# MB_main.net
KiCad netlist of a schematic drawn in Altium Designer
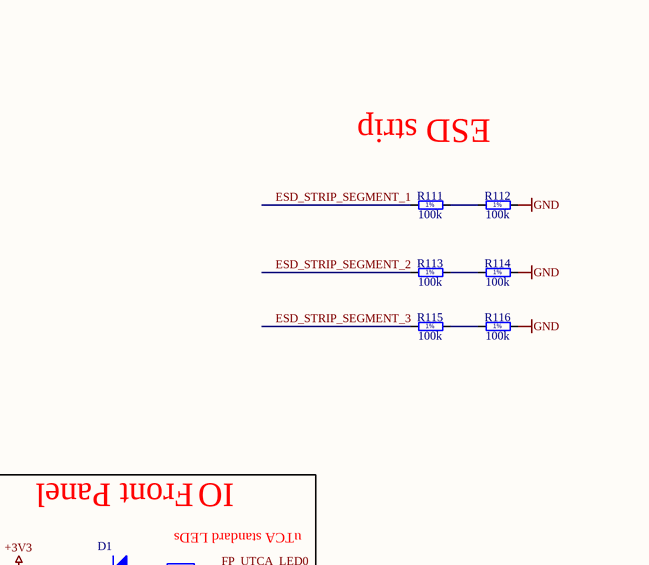
[diagram p0: MB_main.SchDoc, top left]
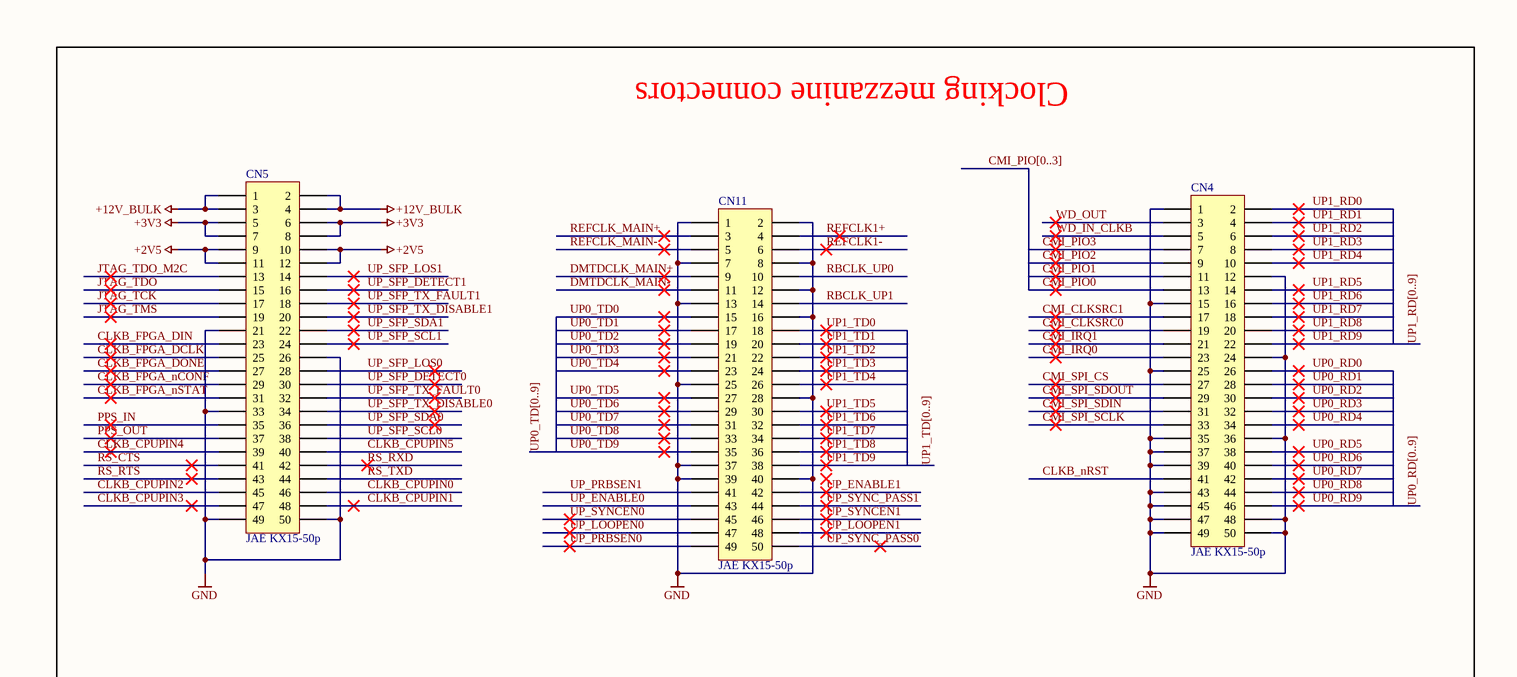
[diagram p1: MB_main.SchDoc, top middle]
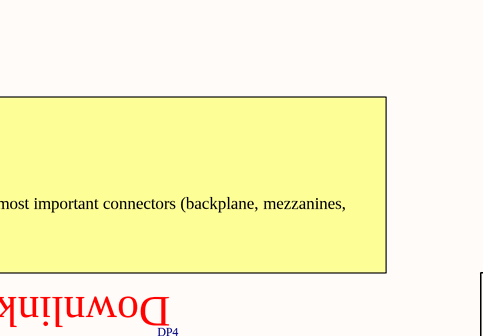
[diagram p2: MB_main.SchDoc, top right]
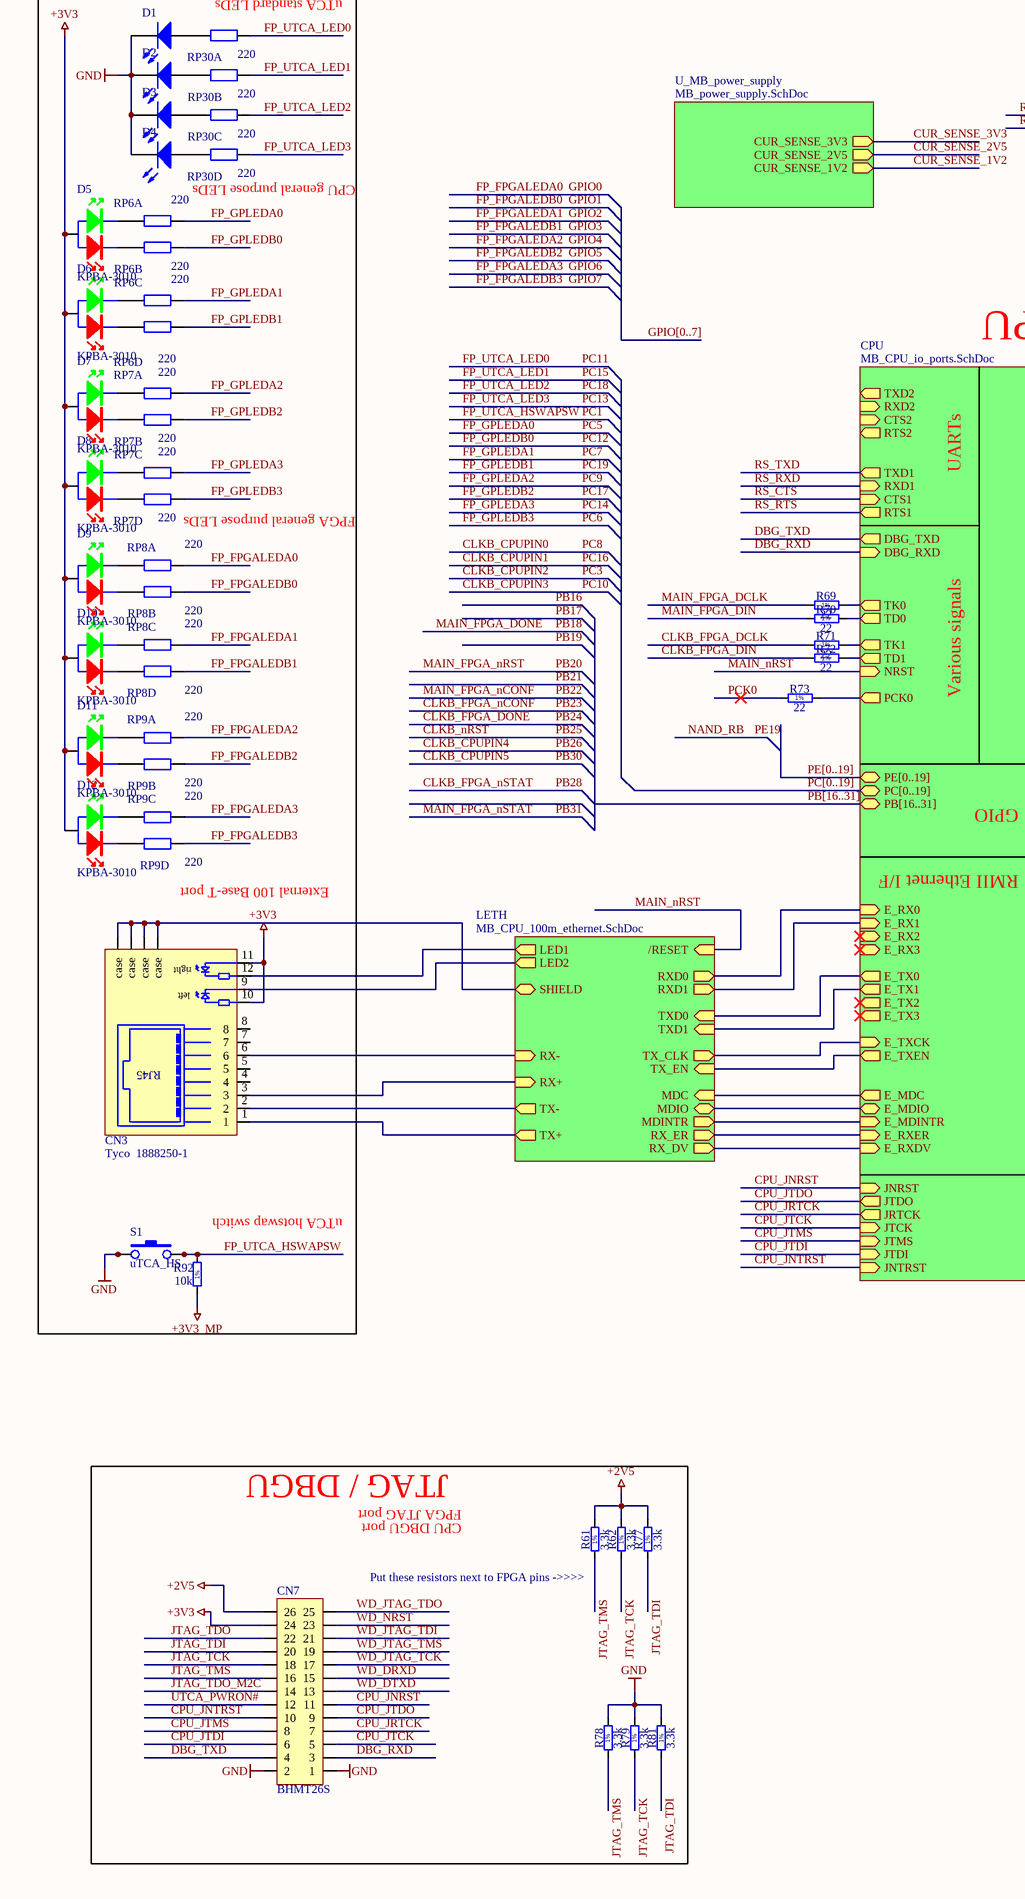
[diagram p3: MB_main.SchDoc, bottom left]
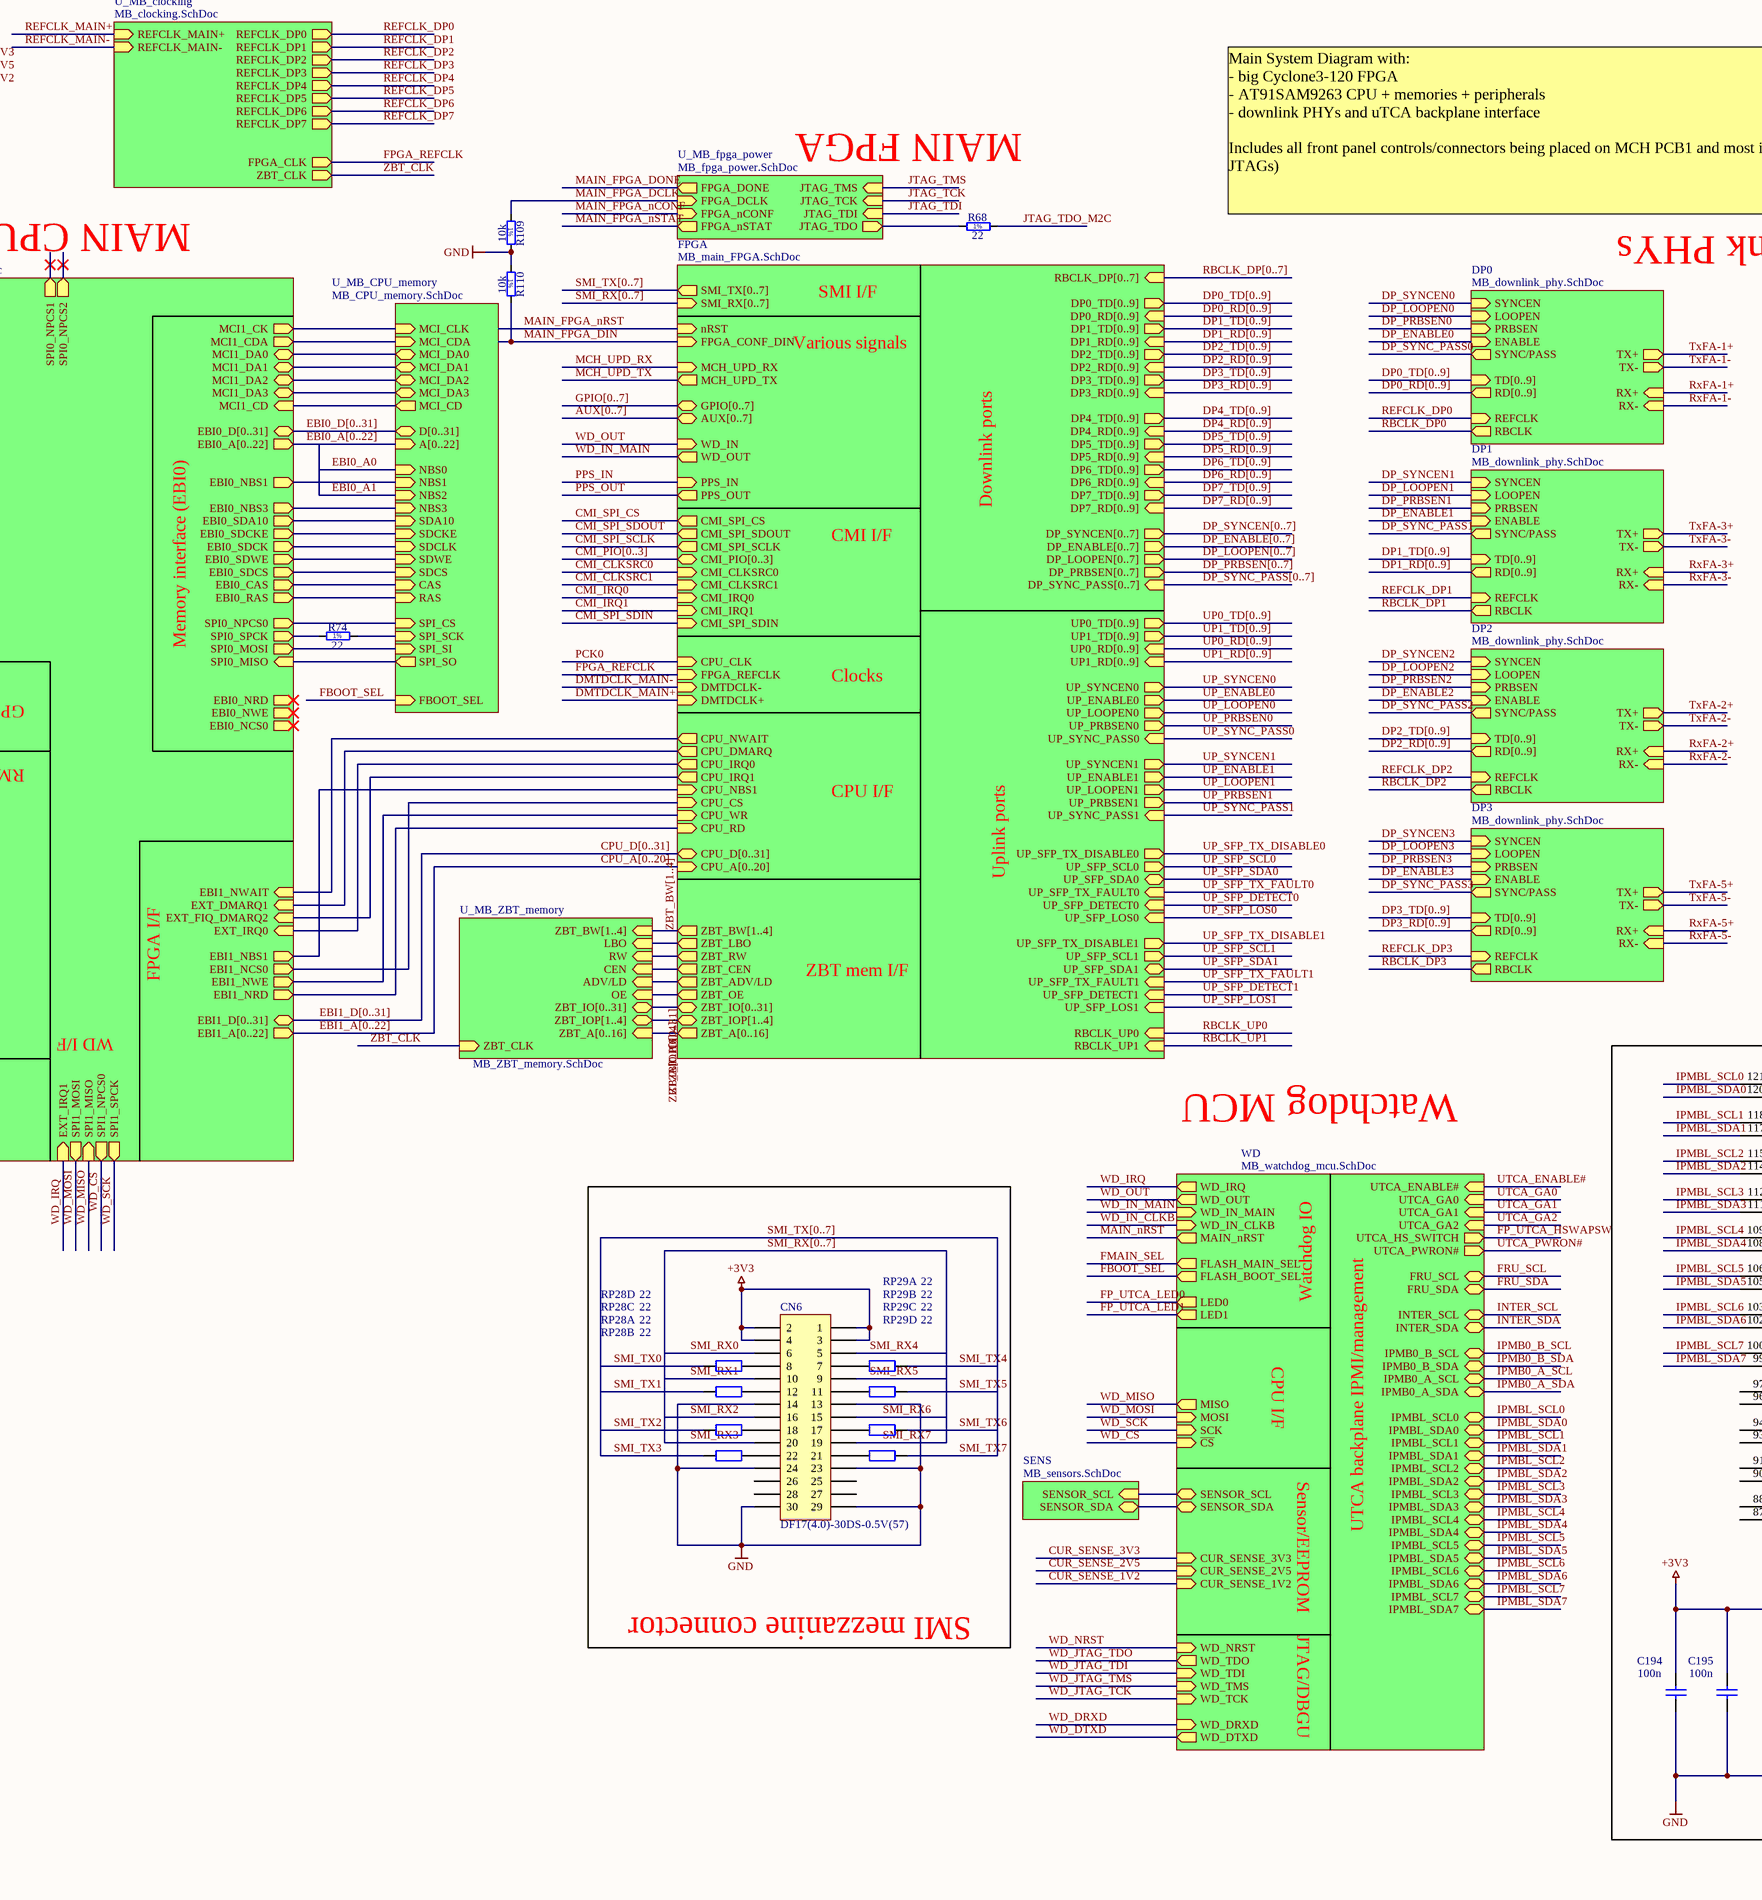
[diagram p4: MB_main.SchDoc, bottom middle]
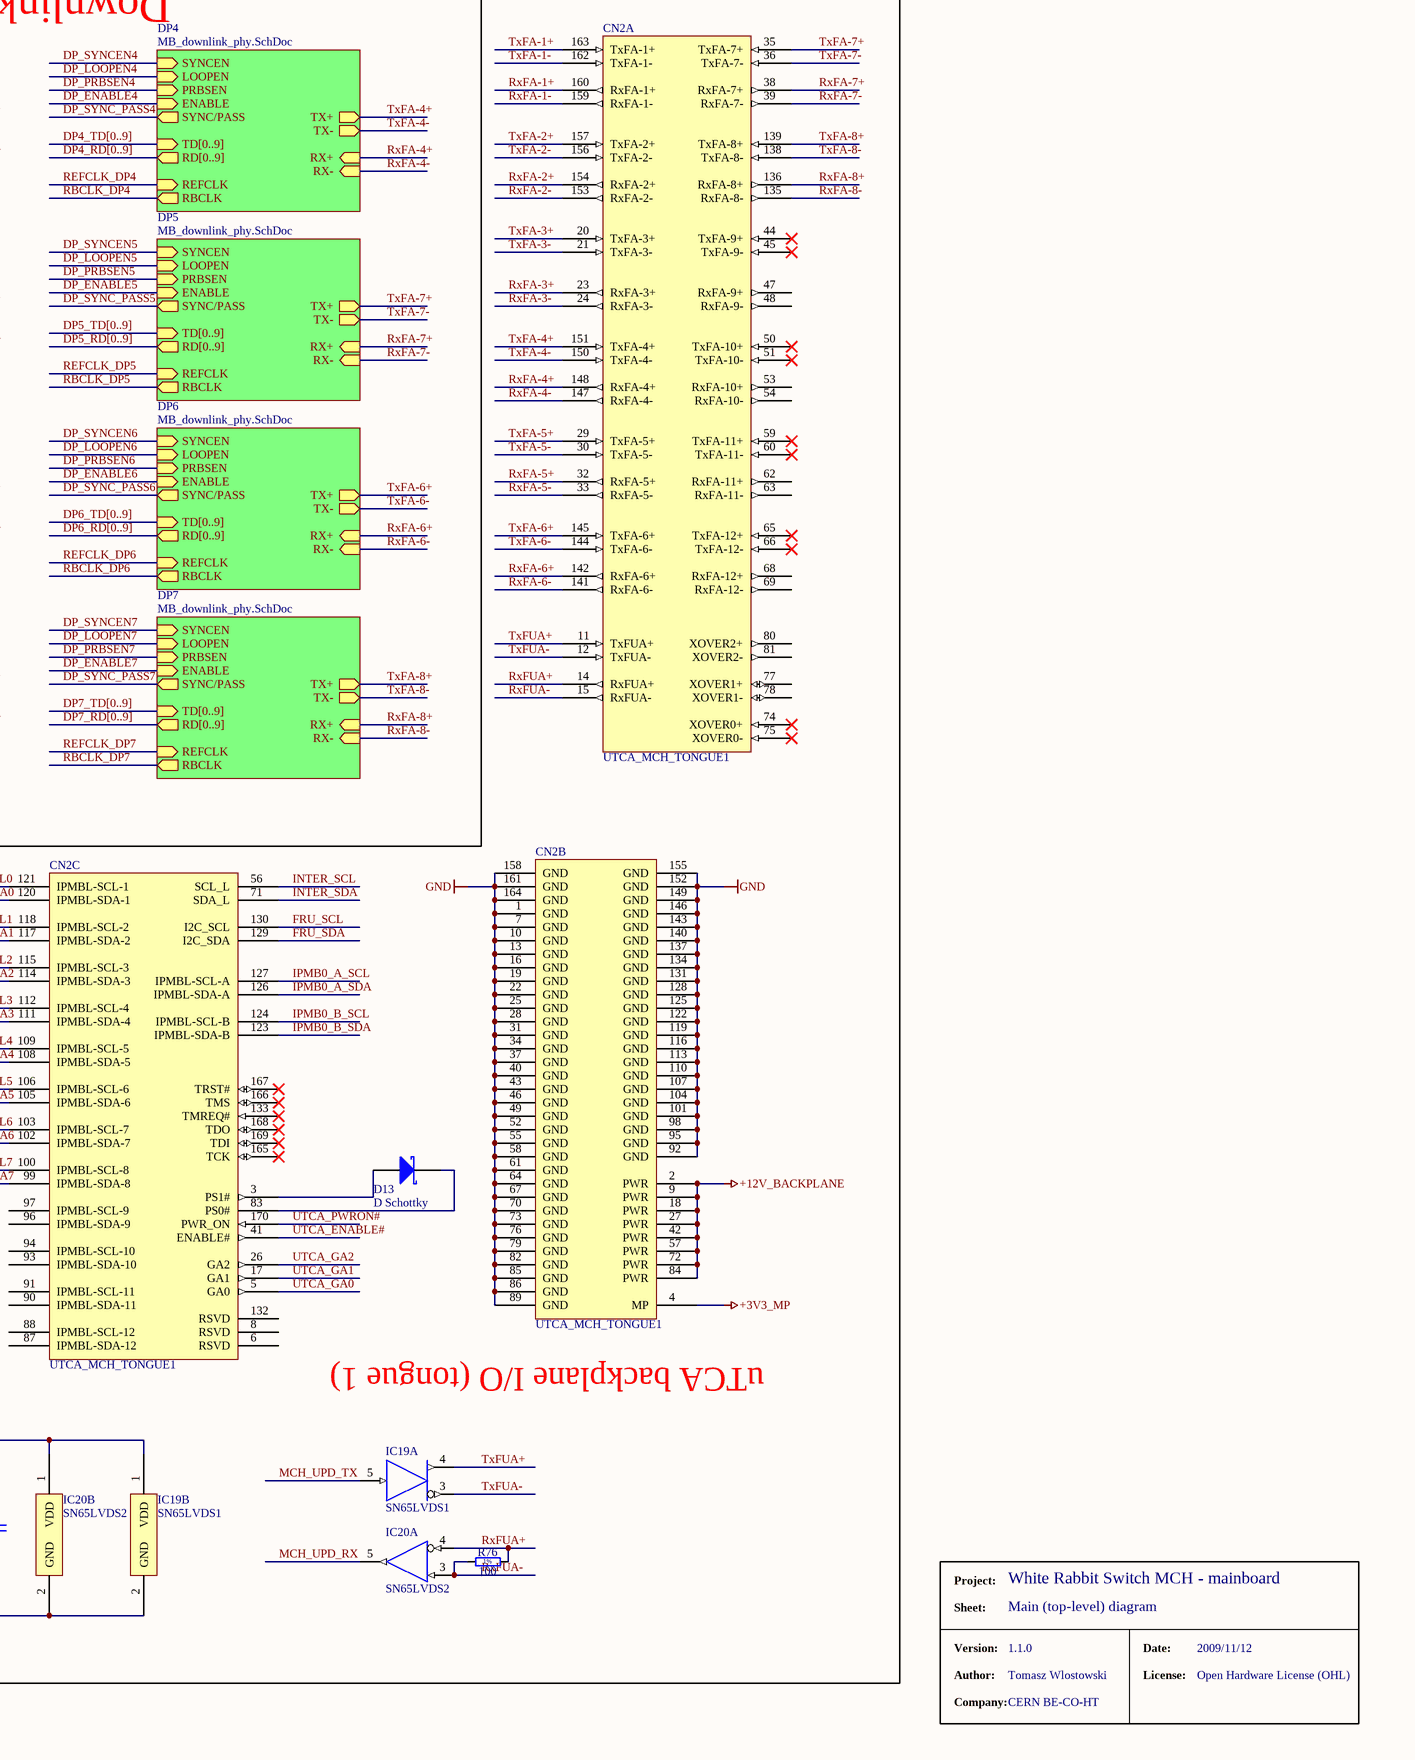
[diagram p5: MB_main.SchDoc, bottom right]

(export (version "E")
  (design (tool "Eeschema 10.0.6"))
  (components
    (comp (ref "C194")
      (value "100n")
      (footprint "CAPC1005X55N")
      (description "Non-polarised capacitor")
      (fields
        (field (name "PART NUMBER") "CC0402_100NF_16V_10%_X7R")
        (field (name "VOLTAGE") "16V")
        (field (name "AUTHOR") "CERN DEM JLC")
      )
      (libsource (lib "Capacitors") (part "Capacitor - non polarized"))
    )
    (comp (ref "C195")
      (value "100n")
      (footprint "CAPC1005X55N")
      (description "Non-polarised capacitor")
      (fields
        (field (name "PART NUMBER") "CC0402_100NF_16V_10%_X7R")
        (field (name "VOLTAGE") "16V")
        (field (name "AUTHOR") "CERN DEM JLC")
      )
      (libsource (lib "Capacitors") (part "Capacitor - non polarized"))
    )
    (comp (ref "CN2")
      (value "UTCA_MCH_TONGUE1")
      (description "microTCA MTCA.0 standard MCH connector 1")
      (libsource (lib "wr_switch") (part "UTCA_MCH_TONGUE1"))
    )
    (comp (ref "CN3")
      (value "Tyco  1888250-1")
      (footprint "TYCO_ETHERNET_1888250-1")
      (description "low profile uTCA Ethernet jack (RJ45)")
      (libsource (lib "wr_switch") (part "CON_ETHERNET_TYCO_1888250-1"))
    )
    (comp (ref "CN4")
      (value "JAE KX15-50p")
      (footprint "JAE_KX15_50P")
      (description "multipin B2B connector (plug)")
      (libsource (lib "wr_switch") (part "KX15_50p"))
    )
    (comp (ref "CN5")
      (value "JAE KX15-50p")
      (footprint "JAE_KX15_50P")
      (description "multipin B2B connector (plug)")
      (libsource (lib "wr_switch") (part "KX15_50p"))
    )
    (comp (ref "CN6")
      (value "DF17(4.0)-30DS-0.5V(57)")
      (footprint "DF17-30-SOCKET")
      (description "multipin B2B connector (plug)")
      (libsource (lib "wr_switch") (part "KX15_30p"))
    )
    (comp (ref "CN7")
      (value "BHMT26S")
      (footprint "CONN_HDR_SMD_2mm_2x13")
      (description "1.27 mm dual row goldpin")
      (libsource (lib "wr_switch") (part "CONN_2x13 2"))
    )
    (comp (ref "CN11")
      (value "JAE KX15-50p")
      (footprint "JAE_KX15_50P")
      (description "multipin B2B connector (plug)")
      (libsource (lib "wr_switch") (part "KX15_50p"))
    )
    (comp (ref "D1")
      (value "LED red")
      (footprint "CD1608-0603")
      (description "Chip LED (any color)")
      (fields (field (name "PUBLISHER") "Altium Limited"))
      (libsource (lib "wr_switch") (part "LED0"))
    )
    (comp (ref "D2")
      (value "LED green")
      (footprint "CD1608-0603")
      (description "Chip LED (any color)")
      (fields (field (name "PUBLISHER") "Altium Limited"))
      (libsource (lib "wr_switch") (part "LED0"))
    )
    (comp (ref "D3")
      (value "LED blue")
      (footprint "CD1608-0603")
      (description "Chip LED (any color)")
      (fields (field (name "PUBLISHER") "Altium Limited"))
      (libsource (lib "wr_switch") (part "LED0"))
    )
    (comp (ref "D4")
      (value "LED orange")
      (footprint "CD1608-0603")
      (description "Chip LED (any color)")
      (fields (field (name "PUBLISHER") "Altium Limited"))
      (libsource (lib "wr_switch") (part "LED0"))
    )
    (comp (ref "D5")
      (value "KPBA-3010")
      (footprint "footprints:DUOLED_LNJ123")
      (description "Dual color LED")
      (libsource (lib "wr_switch") (part "LED_2_colour"))
    )
    (comp (ref "D6")
      (value "KPBA-3010")
      (footprint "footprints:DUOLED_LNJ123")
      (description "Dual color LED")
      (libsource (lib "wr_switch") (part "LED_2_colour"))
    )
    (comp (ref "D7")
      (value "KPBA-3010")
      (footprint "footprints:DUOLED_LNJ123")
      (description "Dual color LED")
      (libsource (lib "wr_switch") (part "LED_2_colour"))
    )
    (comp (ref "D8")
      (value "KPBA-3010")
      (footprint "footprints:DUOLED_LNJ123")
      (description "Dual color LED")
      (libsource (lib "wr_switch") (part "LED_2_colour"))
    )
    (comp (ref "D9")
      (value "KPBA-3010")
      (footprint "footprints:DUOLED_LNJ123")
      (description "Dual color LED")
      (libsource (lib "wr_switch") (part "LED_2_colour"))
    )
    (comp (ref "D10")
      (value "KPBA-3010")
      (footprint "footprints:DUOLED_LNJ123")
      (description "Dual color LED")
      (libsource (lib "wr_switch") (part "LED_2_colour"))
    )
    (comp (ref "D11")
      (value "KPBA-3010")
      (footprint "footprints:DUOLED_LNJ123")
      (description "Dual color LED")
      (libsource (lib "wr_switch") (part "LED_2_colour"))
    )
    (comp (ref "D12")
      (value "KPBA-3010")
      (footprint "footprints:DUOLED_LNJ123")
      (description "Dual color LED")
      (libsource (lib "wr_switch") (part "LED_2_colour"))
    )
    (comp (ref "D13")
      (value "D Schottky")
      (footprint "CD2012-0805")
      (description "Schottky Diode")
      (fields (field (name "PUBLISHER") "Altium Limited"))
      (libsource (lib "wr_switch") (part "D Schottky"))
    )
    (comp (ref "IC19")
      (value "SN65LVDS1")
      (footprint "SOT23-5AL")
      (description "TTL->LVDS buffer")
      (libsource (lib "wr_switch") (part "SN65LVDS1"))
    )
    (comp (ref "IC20")
      (value "SN65LVDS2")
      (footprint "SOT23-5AL")
      (description "LVDS->TTL buffer")
      (libsource (lib "wr_switch") (part "SN65LVDS2"))
    )
    (comp (ref "R61")
      (value "3.3k")
      (footprint "RESC1005X40N")
      (description "Resistor - 1%")
      (fields
        (field (name "PART NUMBER") "R0402_3K3_1%_0.0625W_100PPM")
        (field (name "POWER") "0.0625W")
        (field (name "AUTHOR") "CERN DEM JLC")
      )
      (libsource (lib "Resistors") (part "Resistor - 1%"))
    )
    (comp (ref "R62")
      (value "3.3k")
      (footprint "RESC1005X40N")
      (description "Resistor - 1%")
      (fields
        (field (name "PART NUMBER") "R0402_3K3_1%_0.0625W_100PPM")
        (field (name "POWER") "0.0625W")
        (field (name "AUTHOR") "CERN DEM JLC")
      )
      (libsource (lib "Resistors") (part "Resistor - 1%"))
    )
    (comp (ref "R68")
      (value "22")
      (footprint "RESC1005X40N")
      (description "Resistor - 1%")
      (fields
        (field (name "PART NUMBER") "R0402_22R_1%_0.0625W_100PPM")
        (field (name "POWER") "0.0625W")
        (field (name "AUTHOR") "CERN DEM JLC")
      )
      (libsource (lib "Resistors") (part "Resistor - 1%"))
    )
    (comp (ref "R69")
      (value "22")
      (footprint "RESC1005X40N")
      (description "Resistor - 1%")
      (fields
        (field (name "PART NUMBER") "R0402_22R_1%_0.0625W_100PPM")
        (field (name "POWER") "0.0625W")
        (field (name "AUTHOR") "CERN DEM JLC")
      )
      (libsource (lib "Resistors") (part "Resistor - 1%"))
    )
    (comp (ref "R70")
      (value "22")
      (footprint "RESC1005X40N")
      (description "Resistor - 1%")
      (fields
        (field (name "PART NUMBER") "R0402_22R_1%_0.0625W_100PPM")
        (field (name "POWER") "0.0625W")
        (field (name "AUTHOR") "CERN DEM JLC")
      )
      (libsource (lib "Resistors") (part "Resistor - 1%"))
    )
    (comp (ref "R71")
      (value "22")
      (footprint "RESC1005X40N")
      (description "Resistor - 1%")
      (fields
        (field (name "PART NUMBER") "R0402_22R_1%_0.0625W_100PPM")
        (field (name "POWER") "0.0625W")
        (field (name "AUTHOR") "CERN DEM JLC")
      )
      (libsource (lib "Resistors") (part "Resistor - 1%"))
    )
    (comp (ref "R72")
      (value "22")
      (footprint "RESC1005X40N")
      (description "Resistor - 1%")
      (fields
        (field (name "PART NUMBER") "R0402_22R_1%_0.0625W_100PPM")
        (field (name "POWER") "0.0625W")
        (field (name "AUTHOR") "CERN DEM JLC")
      )
      (libsource (lib "Resistors") (part "Resistor - 1%"))
    )
    (comp (ref "R73")
      (value "22")
      (footprint "RESC1005X40N")
      (description "Resistor - 1%")
      (fields
        (field (name "PART NUMBER") "R0402_22R_1%_0.0625W_100PPM")
        (field (name "POWER") "0.0625W")
        (field (name "AUTHOR") "CERN DEM JLC")
      )
      (libsource (lib "Resistors") (part "Resistor - 1%"))
    )
    (comp (ref "R74")
      (value "22")
      (footprint "RESC1005X40N")
      (description "Resistor - 1%")
      (fields
        (field (name "PART NUMBER") "R0402_22R_1%_0.0625W_100PPM")
        (field (name "POWER") "0.0625W")
        (field (name "AUTHOR") "CERN DEM JLC")
      )
      (libsource (lib "Resistors") (part "Resistor - 1%"))
    )
    (comp (ref "R76")
      (value "100")
      (footprint "RESC1005X40N")
      (description "Resistor - 1%")
      (fields
        (field (name "PART NUMBER") "R0402_100R_1%_0.0625W_100PPM")
        (field (name "POWER") "0.0625W")
        (field (name "AUTHOR") "CERN DEM JLC")
      )
      (libsource (lib "Resistors") (part "Resistor - 1%"))
    )
    (comp (ref "R77")
      (value "3.3k")
      (footprint "RESC1005X40N")
      (description "Resistor - 1%")
      (fields
        (field (name "PART NUMBER") "R0402_3K3_1%_0.0625W_100PPM")
        (field (name "POWER") "0.0625W")
        (field (name "AUTHOR") "CERN DEM JLC")
      )
      (libsource (lib "Resistors") (part "Resistor - 1%"))
    )
    (comp (ref "R78")
      (value "3.3k")
      (footprint "RESC1005X40N")
      (description "Resistor - 1%")
      (fields
        (field (name "PART NUMBER") "R0402_3K3_1%_0.0625W_100PPM")
        (field (name "POWER") "0.0625W")
        (field (name "AUTHOR") "CERN DEM JLC")
      )
      (libsource (lib "Resistors") (part "Resistor - 1%"))
    )
    (comp (ref "R79")
      (value "3.3k")
      (footprint "RESC1005X40N")
      (description "Resistor - 1%")
      (fields
        (field (name "PART NUMBER") "R0402_3K3_1%_0.0625W_100PPM")
        (field (name "POWER") "0.0625W")
        (field (name "AUTHOR") "CERN DEM JLC")
      )
      (libsource (lib "Resistors") (part "Resistor - 1%"))
    )
    (comp (ref "R81")
      (value "3.3k")
      (footprint "RESC1005X40N")
      (description "Resistor - 1%")
      (fields
        (field (name "PART NUMBER") "R0402_3K3_1%_0.0625W_100PPM")
        (field (name "POWER") "0.0625W")
        (field (name "AUTHOR") "CERN DEM JLC")
      )
      (libsource (lib "Resistors") (part "Resistor - 1%"))
    )
    (comp (ref "R92")
      (value "10k")
      (footprint "RESC1005X40N")
      (description "Resistor - 1%")
      (fields
        (field (name "PART NUMBER") "R0402_10K_1%_0.0625W_100PPM")
        (field (name "POWER") "0.0625W")
        (field (name "AUTHOR") "CERN DEM JLC")
      )
      (libsource (lib "Resistors") (part "Resistor - 1%"))
    )
    (comp (ref "R109")
      (value "10k")
      (footprint "RESC1005X40N")
      (description "Resistor - 1%")
      (fields
        (field (name "PART NUMBER") "R0402_10K_1%_0.0625W_100PPM")
        (field (name "POWER") "0.0625W")
        (field (name "AUTHOR") "CERN DEM JLC")
      )
      (libsource (lib "Resistors") (part "Resistor - 1%"))
    )
    (comp (ref "R110")
      (value "10k")
      (footprint "RESC1005X40N")
      (description "Resistor - 1%")
      (fields
        (field (name "PART NUMBER") "R0402_10K_1%_0.0625W_100PPM")
        (field (name "POWER") "0.0625W")
        (field (name "AUTHOR") "CERN DEM JLC")
      )
      (libsource (lib "Resistors") (part "Resistor - 1%"))
    )
    (comp (ref "R111")
      (value "100k")
      (footprint "RESC3216X65N")
      (description "Resistor - 1%")
      (fields
        (field (name "PART NUMBER") "R1206_100K_1%_0.25W_100PPM")
        (field (name "POWER") "0.25W")
        (field (name "AUTHOR") "CERN DEM JLC")
      )
      (libsource (lib "Resistors") (part "Resistor - 1%"))
    )
    (comp (ref "R112")
      (value "100k")
      (footprint "RESC3216X65N")
      (description "Resistor - 1%")
      (fields
        (field (name "PART NUMBER") "R1206_100K_1%_0.25W_100PPM")
        (field (name "POWER") "0.25W")
        (field (name "AUTHOR") "CERN DEM JLC")
      )
      (libsource (lib "Resistors") (part "Resistor - 1%"))
    )
    (comp (ref "R113")
      (value "100k")
      (footprint "RESC3216X65N")
      (description "Resistor - 1%")
      (fields
        (field (name "PART NUMBER") "R1206_100K_1%_0.25W_100PPM")
        (field (name "POWER") "0.25W")
        (field (name "AUTHOR") "CERN DEM JLC")
      )
      (libsource (lib "Resistors") (part "Resistor - 1%"))
    )
    (comp (ref "R114")
      (value "100k")
      (footprint "RESC3216X65N")
      (description "Resistor - 1%")
      (fields
        (field (name "PART NUMBER") "R1206_100K_1%_0.25W_100PPM")
        (field (name "POWER") "0.25W")
        (field (name "AUTHOR") "CERN DEM JLC")
      )
      (libsource (lib "Resistors") (part "Resistor - 1%"))
    )
    (comp (ref "R115")
      (value "100k")
      (footprint "RESC3216X65N")
      (description "Resistor - 1%")
      (fields
        (field (name "PART NUMBER") "R1206_100K_1%_0.25W_100PPM")
        (field (name "POWER") "0.25W")
        (field (name "AUTHOR") "CERN DEM JLC")
      )
      (libsource (lib "Resistors") (part "Resistor - 1%"))
    )
    (comp (ref "R116")
      (value "100k")
      (footprint "RESC3216X65N")
      (description "Resistor - 1%")
      (fields
        (field (name "PART NUMBER") "R1206_100K_1%_0.25W_100PPM")
        (field (name "POWER") "0.25W")
        (field (name "AUTHOR") "CERN DEM JLC")
      )
      (libsource (lib "Resistors") (part "Resistor - 1%"))
    )
    (comp (ref "RP6")
      (value "220")
      (footprint "YC124")
      (description "4-resistor pack")
      (fields (field (name "Comment") "220R 0804"))
      (libsource (lib "wr_switch") (part "Res_Pack4_220R_YC124_1"))
    )
    (comp (ref "RP7")
      (value "220")
      (footprint "YC124")
      (description "4-resistor pack")
      (fields (field (name "Comment") "220R 0804"))
      (libsource (lib "wr_switch") (part "Res_Pack4_220R_YC124_1"))
    )
    (comp (ref "RP8")
      (value "220")
      (footprint "YC124")
      (description "4-resistor pack")
      (fields (field (name "Comment") "220R 0804"))
      (libsource (lib "wr_switch") (part "Res_Pack4_220R_YC124_1"))
    )
    (comp (ref "RP9")
      (value "220")
      (footprint "YC124")
      (description "4-resistor pack")
      (fields (field (name "Comment") "220R 0804"))
      (libsource (lib "wr_switch") (part "Res_Pack4_220R_YC124_1"))
    )
    (comp (ref "RP28")
      (value "22")
      (footprint "YC124")
      (description "4-resistor pack")
      (fields (field (name "Comment") "22R 0804"))
      (libsource (lib "wr_switch") (part "Res_Pack4_22R_YC124"))
    )
    (comp (ref "RP29")
      (value "22")
      (footprint "YC124")
      (description "4-resistor pack")
      (fields (field (name "Comment") "22R 0804"))
      (libsource (lib "wr_switch") (part "Res_Pack4_22R_YC124"))
    )
    (comp (ref "RP30")
      (value "220")
      (footprint "YC124")
      (description "4-resistor pack")
      (fields (field (name "Comment") "220R 0804"))
      (libsource (lib "wr_switch") (part "Res_Pack4_220R_YC124_1"))
    )
    (comp (ref "S1")
      (value "uTCA_HS")
      (footprint "uTCA_HOTSWAP_SWITCH")
      (description "Push button")
      (libsource (lib "wr_switch") (part "uTCA_HOTSWAP_SWITCH"))
    )
  )
  (nets
    (net (code "356") (name "+2V5") (class "Default")
      (node (ref "CN5") (pin "10") (pinfunction "10_10") (pintype "passive"))
      (node (ref "CN5") (pin "11") (pinfunction "11_11") (pintype "passive"))
      (node (ref "CN5") (pin "12") (pinfunction "12_12") (pintype "passive"))
      (node (ref "CN5") (pin "9") (pinfunction "9_9") (pintype "passive"))
      (node (ref "CN7") (pin "26") (pinfunction "26_26") (pintype "passive"))
      (node (ref "R61") (pin "2") (pinfunction "2_2") (pintype "passive"))
      (node (ref "R62") (pin "2") (pinfunction "2_2") (pintype "passive"))
      (node (ref "R77") (pin "2") (pinfunction "2_2") (pintype "passive"))
    )
    (net (code "357") (name "+3V3") (class "Default")
      (node (ref "C194") (pin "2") (pinfunction "2_2") (pintype "passive"))
      (node (ref "C195") (pin "2") (pinfunction "2_2") (pintype "passive"))
      (node (ref "CN3") (pin "10") (pinfunction "D1_10") (pintype "passive"))
      (node (ref "CN3") (pin "11") (pinfunction "D4_11") (pintype "passive"))
      (node (ref "CN5") (pin "5") (pinfunction "5_5") (pintype "passive"))
      (node (ref "CN5") (pin "6") (pinfunction "6_6") (pintype "passive"))
      (node (ref "CN5") (pin "7") (pinfunction "7_7") (pintype "passive"))
      (node (ref "CN5") (pin "8") (pinfunction "8_8") (pintype "passive"))
      (node (ref "CN6") (pin "1") (pinfunction "1_1") (pintype "passive"))
      (node (ref "CN6") (pin "2") (pinfunction "2_2") (pintype "passive"))
      (node (ref "CN6") (pin "3") (pinfunction "3_3") (pintype "passive"))
      (node (ref "CN6") (pin "4") (pinfunction "4_4") (pintype "passive"))
      (node (ref "CN7") (pin "24") (pinfunction "24_24") (pintype "passive"))
      (node (ref "D10") (pin "A") (pinfunction "A_A") (pintype "passive"))
      (node (ref "D11") (pin "A") (pinfunction "A_A") (pintype "passive"))
      (node (ref "D12") (pin "A") (pinfunction "A_A") (pintype "passive"))
      (node (ref "D5") (pin "A") (pinfunction "A_A") (pintype "passive"))
      (node (ref "D6") (pin "A") (pinfunction "A_A") (pintype "passive"))
      (node (ref "D7") (pin "A") (pinfunction "A_A") (pintype "passive"))
      (node (ref "D8") (pin "A") (pinfunction "A_A") (pintype "passive"))
      (node (ref "D9") (pin "A") (pinfunction "A_A") (pintype "passive"))
      (node (ref "IC19") (pin "1") (pinfunction "VDD_1") (pintype "passive"))
      (node (ref "IC20") (pin "1") (pinfunction "VDD_1") (pintype "passive"))
    )
    (net (code "358") (name "+3V3_MP") (class "Default")
      (node (ref "CN2") (pin "4") (pinfunction "MP_4") (pintype "power_in"))
      (node (ref "R92") (pin "1") (pinfunction "1_1") (pintype "passive"))
    )
    (net (code "359") (name "+12V_BACKPLANE") (class "Default")
      (node (ref "CN2") (pin "18") (pinfunction "PWR_18") (pintype "power_in"))
      (node (ref "CN2") (pin "2") (pinfunction "PWR_2") (pintype "power_in"))
      (node (ref "CN2") (pin "27") (pinfunction "PWR_27") (pintype "power_in"))
      (node (ref "CN2") (pin "42") (pinfunction "PWR_42") (pintype "power_in"))
      (node (ref "CN2") (pin "57") (pinfunction "PWR_57") (pintype "power_in"))
      (node (ref "CN2") (pin "72") (pinfunction "PWR_72") (pintype "power_in"))
      (node (ref "CN2") (pin "84") (pinfunction "PWR_84") (pintype "power_in"))
      (node (ref "CN2") (pin "9") (pinfunction "PWR_9") (pintype "power_in"))
    )
    (net (code "360") (name "+12V_BULK") (class "Default")
      (node (ref "CN5") (pin "1") (pinfunction "1_1") (pintype "passive"))
      (node (ref "CN5") (pin "2") (pinfunction "2_2") (pintype "passive"))
      (node (ref "CN5") (pin "3") (pinfunction "3_3") (pintype "passive"))
      (node (ref "CN5") (pin "4") (pinfunction "4_4") (pintype "passive"))
    )
    (net (code "362") (name "/CLKB_FPGA_DCLK") (class "Default")
      (node (ref "CN5") (pin "25") (pinfunction "25_25") (pintype "passive"))
      (node (ref "R71") (pin "1") (pinfunction "1_1") (pintype "passive"))
    )
    (net (code "363") (name "/CLKB_FPGA_DIN") (class "Default")
      (node (ref "CN5") (pin "23") (pinfunction "23_23") (pintype "passive"))
      (node (ref "R72") (pin "1") (pinfunction "1_1") (pintype "passive"))
    )
    (net (code "364") (name "/CMI_CLKSRC0") (class "Default")
      (node (ref "CN4") (pin "19") (pinfunction "19_19") (pintype "passive"))
    )
    (net (code "365") (name "/CMI_CLKSRC1") (class "Default")
      (node (ref "CN4") (pin "17") (pinfunction "17_17") (pintype "passive"))
    )
    (net (code "366") (name "/CMI_IRQ0") (class "Default")
      (node (ref "CN4") (pin "23") (pinfunction "23_23") (pintype "passive"))
    )
    (net (code "367") (name "/CMI_IRQ1") (class "Default")
      (node (ref "CN4") (pin "21") (pinfunction "21_21") (pintype "passive"))
    )
    (net (code "368") (name "/CMI_PIO0") (class "Default")
      (node (ref "CN4") (pin "13") (pinfunction "13_13") (pintype "passive"))
    )
    (net (code "369") (name "/CMI_PIO1") (class "Default")
      (node (ref "CN4") (pin "11") (pinfunction "11_11") (pintype "passive"))
    )
    (net (code "370") (name "/CMI_PIO2") (class "Default")
      (node (ref "CN4") (pin "9") (pinfunction "9_9") (pintype "passive"))
    )
    (net (code "371") (name "/CMI_PIO3") (class "Default")
      (node (ref "CN4") (pin "7") (pinfunction "7_7") (pintype "passive"))
    )
    (net (code "373") (name "/CMI_SPI_CS") (class "Default")
      (node (ref "CN4") (pin "27") (pinfunction "27_27") (pintype "passive"))
    )
    (net (code "374") (name "/CMI_SPI_SCLK") (class "Default")
      (node (ref "CN4") (pin "33") (pinfunction "33_33") (pintype "passive"))
    )
    (net (code "375") (name "/CMI_SPI_SDIN") (class "Default")
      (node (ref "CN4") (pin "31") (pinfunction "31_31") (pintype "passive"))
    )
    (net (code "376") (name "/CMI_SPI_SDOUT") (class "Default")
      (node (ref "CN4") (pin "29") (pinfunction "29_29") (pintype "passive"))
    )
    (net (code "382") (name "/CPU_JNRST") (class "Default")
      (node (ref "CN7") (pin "11") (pinfunction "11_11") (pintype "passive"))
    )
    (net (code "383") (name "/CPU_JNTRST") (class "Default")
      (node (ref "CN7") (pin "10") (pinfunction "10_10") (pintype "passive"))
    )
    (net (code "384") (name "/CPU_JRTCK") (class "Default")
      (node (ref "CN7") (pin "7") (pinfunction "7_7") (pintype "passive"))
    )
    (net (code "385") (name "/CPU_JTCK") (class "Default")
      (node (ref "CN7") (pin "5") (pinfunction "5_5") (pintype "passive"))
    )
    (net (code "386") (name "/CPU_JTDI") (class "Default")
      (node (ref "CN7") (pin "6") (pinfunction "6_6") (pintype "passive"))
    )
    (net (code "387") (name "/CPU_JTDO") (class "Default")
      (node (ref "CN7") (pin "9") (pinfunction "9_9") (pintype "passive"))
    )
    (net (code "388") (name "/CPU_JTMS") (class "Default")
      (node (ref "CN7") (pin "8") (pinfunction "8_8") (pintype "passive"))
    )
    (net (code "394") (name "/DBG_RXD") (class "Default")
      (node (ref "CN7") (pin "3") (pinfunction "3_3") (pintype "passive"))
    )
    (net (code "395") (name "/DBG_TXD") (class "Default")
      (node (ref "CN7") (pin "4") (pinfunction "4_4") (pintype "passive"))
    )
    (net (code "396") (name "/DMTDCLK_MAIN+") (class "Default")
      (node (ref "CN11") (pin "9") (pinfunction "9_9") (pintype "passive"))
    )
    (net (code "397") (name "/DMTDCLK_MAIN-") (class "Default")
      (node (ref "CN11") (pin "11") (pinfunction "11_11") (pintype "passive"))
    )
    (net (code "479") (name "/ESD_STRIP_SEGMENT_1") (class "Default")
      (node (ref "R111") (pin "1") (pinfunction "1_1") (pintype "passive"))
    )
    (net (code "480") (name "/ESD_STRIP_SEGMENT_2") (class "Default")
      (node (ref "R113") (pin "1") (pinfunction "1_1") (pintype "passive"))
    )
    (net (code "481") (name "/ESD_STRIP_SEGMENT_3") (class "Default")
      (node (ref "R115") (pin "1") (pinfunction "1_1") (pintype "passive"))
    )
    (net (code "494") (name "/FRU_SCL") (class "Default")
      (node (ref "CN2") (pin "130") (pinfunction "I2C_SCL_130") (pintype "open_collector"))
    )
    (net (code "495") (name "/FRU_SDA") (class "Default")
      (node (ref "CN2") (pin "129") (pinfunction "I2C_SDA_129") (pintype "open_collector"))
    )
    (net (code "496") (name "/GPIO0") (class "Default")
      (node (ref "RP8") (pin "8") (pinfunction "B_8") (pintype "passive"))
    )
    (net (code "497") (name "/GPIO1") (class "Default")
      (node (ref "RP8") (pin "7") (pinfunction "B_7") (pintype "passive"))
    )
    (net (code "498") (name "/GPIO2") (class "Default")
      (node (ref "RP8") (pin "6") (pinfunction "B_6") (pintype "passive"))
    )
    (net (code "499") (name "/GPIO3") (class "Default")
      (node (ref "RP8") (pin "5") (pinfunction "B_5") (pintype "passive"))
    )
    (net (code "500") (name "/GPIO4") (class "Default")
      (node (ref "RP9") (pin "8") (pinfunction "B_8") (pintype "passive"))
    )
    (net (code "501") (name "/GPIO5") (class "Default")
      (node (ref "RP9") (pin "7") (pinfunction "B_7") (pintype "passive"))
    )
    (net (code "502") (name "/GPIO6") (class "Default")
      (node (ref "RP9") (pin "6") (pinfunction "B_6") (pintype "passive"))
    )
    (net (code "503") (name "/GPIO7") (class "Default")
      (node (ref "RP9") (pin "5") (pinfunction "B_5") (pintype "passive"))
    )
    (net (code "505") (name "/INTER_SCL") (class "Default")
      (node (ref "CN2") (pin "56") (pinfunction "SCL_L_56") (pintype "open_collector"))
    )
    (net (code "506") (name "/INTER_SDA") (class "Default")
      (node (ref "CN2") (pin "71") (pinfunction "SDA_L_71") (pintype "open_collector"))
    )
    (net (code "507") (name "/IPMB0_A_SCL") (class "Default")
      (node (ref "CN2") (pin "127") (pinfunction "IPMBL-SCL-A_127") (pintype "open_collector"))
    )
    (net (code "508") (name "/IPMB0_A_SDA") (class "Default")
      (node (ref "CN2") (pin "126") (pinfunction "IPMBL-SDA-A_126") (pintype "open_collector"))
    )
    (net (code "509") (name "/IPMB0_B_SCL") (class "Default")
      (node (ref "CN2") (pin "124") (pinfunction "IPMBL-SCL-B_124") (pintype "open_collector"))
    )
    (net (code "510") (name "/IPMB0_B_SDA") (class "Default")
      (node (ref "CN2") (pin "123") (pinfunction "IPMBL-SDA-B_123") (pintype "open_collector"))
    )
    (net (code "511") (name "/IPMBL_SCL0") (class "Default")
      (node (ref "CN2") (pin "121") (pinfunction "IPMBL-SCL-1_121") (pintype "open_collector"))
    )
    (net (code "512") (name "/IPMBL_SCL1") (class "Default")
      (node (ref "CN2") (pin "118") (pinfunction "IPMBL-SCL-2_118") (pintype "open_collector"))
    )
    (net (code "513") (name "/IPMBL_SCL2") (class "Default")
      (node (ref "CN2") (pin "115") (pinfunction "IPMBL-SCL-3_115") (pintype "open_collector"))
    )
    (net (code "514") (name "/IPMBL_SCL3") (class "Default")
      (node (ref "CN2") (pin "112") (pinfunction "IPMBL-SCL-4_112") (pintype "open_collector"))
    )
    (net (code "515") (name "/IPMBL_SCL4") (class "Default")
      (node (ref "CN2") (pin "109") (pinfunction "IPMBL-SCL-5_109") (pintype "open_collector"))
    )
    (net (code "516") (name "/IPMBL_SCL5") (class "Default")
      (node (ref "CN2") (pin "106") (pinfunction "IPMBL-SCL-6_106") (pintype "open_collector"))
    )
    (net (code "517") (name "/IPMBL_SCL6") (class "Default")
      (node (ref "CN2") (pin "103") (pinfunction "IPMBL-SCL-7_103") (pintype "open_collector"))
    )
    (net (code "518") (name "/IPMBL_SCL7") (class "Default")
      (node (ref "CN2") (pin "100") (pinfunction "IPMBL-SCL-8_100") (pintype "open_collector"))
    )
    (net (code "519") (name "/IPMBL_SDA0") (class "Default")
      (node (ref "CN2") (pin "120") (pinfunction "IPMBL-SDA-1_120") (pintype "open_collector"))
    )
    (net (code "520") (name "/IPMBL_SDA1") (class "Default")
      (node (ref "CN2") (pin "117") (pinfunction "IPMBL-SDA-2_117") (pintype "open_collector"))
    )
    (net (code "521") (name "/IPMBL_SDA2") (class "Default")
      (node (ref "CN2") (pin "114") (pinfunction "IPMBL-SDA-3_114") (pintype "open_collector"))
    )
    (net (code "522") (name "/IPMBL_SDA3") (class "Default")
      (node (ref "CN2") (pin "111") (pinfunction "IPMBL-SDA-4_111") (pintype "open_collector"))
    )
    (net (code "523") (name "/IPMBL_SDA4") (class "Default")
      (node (ref "CN2") (pin "108") (pinfunction "IPMBL-SDA-5_108") (pintype "open_collector"))
    )
    (net (code "524") (name "/IPMBL_SDA5") (class "Default")
      (node (ref "CN2") (pin "105") (pinfunction "IPMBL-SDA-6_105") (pintype "open_collector"))
    )
    (net (code "525") (name "/IPMBL_SDA6") (class "Default")
      (node (ref "CN2") (pin "102") (pinfunction "IPMBL-SDA-7_102") (pintype "open_collector"))
    )
    (net (code "526") (name "/IPMBL_SDA7") (class "Default")
      (node (ref "CN2") (pin "99") (pinfunction "IPMBL-SDA-8_99") (pintype "open_collector"))
    )
    (net (code "527") (name "/JTAG_TCK") (class "Default")
      (node (ref "CN5") (pin "17") (pinfunction "17_17") (pintype "passive"))
      (node (ref "CN7") (pin "18") (pinfunction "18_18") (pintype "passive"))
      (node (ref "R62") (pin "1") (pinfunction "1_1") (pintype "passive"))
      (node (ref "R79") (pin "1") (pinfunction "1_1") (pintype "passive"))
    )
    (net (code "528") (name "/JTAG_TDI") (class "Default")
      (node (ref "CN7") (pin "20") (pinfunction "20_20") (pintype "passive"))
      (node (ref "R77") (pin "1") (pinfunction "1_1") (pintype "passive"))
      (node (ref "R81") (pin "1") (pinfunction "1_1") (pintype "passive"))
    )
    (net (code "529") (name "/JTAG_TDO") (class "Default")
      (node (ref "CN5") (pin "15") (pinfunction "15_15") (pintype "passive"))
      (node (ref "CN7") (pin "22") (pinfunction "22_22") (pintype "passive"))
    )
    (net (code "530") (name "/JTAG_TDO_1") (class "Default")
      (node (ref "R68") (pin "1") (pinfunction "1_1") (pintype "passive"))
    )
    (net (code "531") (name "/JTAG_TDO_M2C") (class "Default")
      (node (ref "CN5") (pin "13") (pinfunction "13_13") (pintype "passive"))
      (node (ref "CN7") (pin "14") (pinfunction "14_14") (pintype "passive"))
      (node (ref "R68") (pin "2") (pinfunction "2_2") (pintype "passive"))
    )
    (net (code "532") (name "/JTAG_TMS") (class "Default")
      (node (ref "CN5") (pin "19") (pinfunction "19_19") (pintype "passive"))
      (node (ref "CN7") (pin "16") (pinfunction "16_16") (pintype "passive"))
      (node (ref "R61") (pin "1") (pinfunction "1_1") (pintype "passive"))
      (node (ref "R78") (pin "1") (pinfunction "1_1") (pintype "passive"))
    )
    (net (code "533") (name "/LED1") (class "Default")
      (node (ref "CN3") (pin "12") (pinfunction "D3_12") (pintype "passive"))
    )
    (net (code "534") (name "/LED2") (class "Default")
      (node (ref "CN3") (pin "9") (pinfunction "D2_9") (pintype "passive"))
    )
    (net (code "535") (name "/MAIN_FPGA_DCLK") (class "Default")
      (node (ref "R109") (pin "1") (pinfunction "1_1") (pintype "passive"))
      (node (ref "R69") (pin "1") (pinfunction "1_1") (pintype "passive"))
    )
    (net (code "536") (name "/MAIN_FPGA_DIN") (class "Default")
      (node (ref "R110") (pin "2") (pinfunction "2_2") (pintype "passive"))
      (node (ref "R70") (pin "1") (pinfunction "1_1") (pintype "passive"))
    )
    (net (code "538") (name "/MCH_UPD_RX") (class "Default")
      (node (ref "IC20") (pin "5") (pinfunction "Q_5") (pintype "output"))
    )
    (net (code "539") (name "/MCH_UPD_TX") (class "Default")
      (node (ref "IC19") (pin "5") (pinfunction "A_5") (pintype "input"))
    )
    (net (code "555") (name "/PB23") (class "Default")
      (node (ref "CN5") (pin "29") (pinfunction "29_29") (pintype "passive"))
    )
    (net (code "556") (name "/PB24") (class "Default")
      (node (ref "CN5") (pin "27") (pinfunction "27_27") (pintype "passive"))
    )
    (net (code "557") (name "/PB25") (class "Default")
      (node (ref "CN4") (pin "41") (pinfunction "41_41") (pintype "passive"))
    )
    (net (code "558") (name "/PB26") (class "Default")
      (node (ref "CN5") (pin "39") (pinfunction "39_39") (pintype "passive"))
    )
    (net (code "559") (name "/PB28") (class "Default")
      (node (ref "CN5") (pin "31") (pinfunction "31_31") (pintype "passive"))
    )
    (net (code "560") (name "/PB30") (class "Default")
      (node (ref "CN5") (pin "40") (pinfunction "40_40") (pintype "passive"))
    )
    (net (code "563") (name "/PC1") (class "Default")
      (node (ref "R92") (pin "2") (pinfunction "2_2") (pintype "passive"))
      (node (ref "S1") (pin "B") (pinfunction "B_B") (pintype "passive"))
      (node (ref "S1") (pin "D") (pinfunction "D_D") (pintype "passive"))
    )
    (net (code "564") (name "/PC3") (class "Default")
      (node (ref "CN5") (pin "45") (pinfunction "45_45") (pintype "passive"))
    )
    (net (code "565") (name "/PC5") (class "Default")
      (node (ref "RP6") (pin "8") (pinfunction "B_8") (pintype "passive"))
    )
    (net (code "566") (name "/PC6") (class "Default")
      (node (ref "RP7") (pin "5") (pinfunction "B_5") (pintype "passive"))
    )
    (net (code "567") (name "/PC7") (class "Default")
      (node (ref "RP6") (pin "6") (pinfunction "B_6") (pintype "passive"))
    )
    (net (code "568") (name "/PC8") (class "Default")
      (node (ref "CN5") (pin "46") (pinfunction "46_46") (pintype "passive"))
    )
    (net (code "569") (name "/PC9") (class "Default")
      (node (ref "RP7") (pin "8") (pinfunction "B_8") (pintype "passive"))
    )
    (net (code "570") (name "/PC10") (class "Default")
      (node (ref "CN5") (pin "47") (pinfunction "47_47") (pintype "passive"))
    )
    (net (code "571") (name "/PC11") (class "Default")
      (node (ref "RP30") (pin "8") (pinfunction "B_8") (pintype "passive"))
    )
    (net (code "572") (name "/PC12") (class "Default")
      (node (ref "RP6") (pin "7") (pinfunction "B_7") (pintype "passive"))
    )
    (net (code "573") (name "/PC13") (class "Default")
      (node (ref "RP30") (pin "5") (pinfunction "B_5") (pintype "passive"))
    )
    (net (code "574") (name "/PC14") (class "Default")
      (node (ref "RP7") (pin "6") (pinfunction "B_6") (pintype "passive"))
    )
    (net (code "575") (name "/PC15") (class "Default")
      (node (ref "RP30") (pin "7") (pinfunction "B_7") (pintype "passive"))
    )
    (net (code "576") (name "/PC16") (class "Default")
      (node (ref "CN5") (pin "48") (pinfunction "48_48") (pintype "passive"))
    )
    (net (code "577") (name "/PC17") (class "Default")
      (node (ref "RP7") (pin "7") (pinfunction "B_7") (pintype "passive"))
    )
    (net (code "578") (name "/PC18") (class "Default")
      (node (ref "RP30") (pin "6") (pinfunction "B_6") (pintype "passive"))
    )
    (net (code "579") (name "/PC19") (class "Default")
      (node (ref "RP6") (pin "5") (pinfunction "B_5") (pintype "passive"))
    )
    (net (code "580") (name "/PCK0") (class "Default")
      (node (ref "R73") (pin "1") (pinfunction "1_1") (pintype "passive"))
    )
    (net (code "581") (name "/PCK0_1") (class "Default")
      (node (ref "R73") (pin "2") (pinfunction "2_2") (pintype "passive"))
    )
    (net (code "585") (name "/PPS_IN") (class "Default")
      (node (ref "CN5") (pin "35") (pinfunction "35_35") (pintype "passive"))
    )
    (net (code "586") (name "/PPS_OUT") (class "Default")
      (node (ref "CN5") (pin "37") (pinfunction "37_37") (pintype "passive"))
    )
    (net (code "596") (name "/RBCLK_UP0") (class "Default")
      (node (ref "CN11") (pin "10") (pinfunction "10_10") (pintype "passive"))
    )
    (net (code "597") (name "/RBCLK_UP1") (class "Default")
      (node (ref "CN11") (pin "14") (pinfunction "14_14") (pintype "passive"))
    )
    (net (code "598") (name "/REFCLK1+") (class "Default")
      (node (ref "CN11") (pin "4") (pinfunction "4_4") (pintype "passive"))
    )
    (net (code "608") (name "/REFCLK1-") (class "Default")
      (node (ref "CN11") (pin "6") (pinfunction "6_6") (pintype "passive"))
    )
    (net (code "609") (name "/REFCLK_MAIN+") (class "Default")
      (node (ref "CN11") (pin "3") (pinfunction "3_3") (pintype "passive"))
    )
    (net (code "610") (name "/REFCLK_MAIN-") (class "Default")
      (node (ref "CN11") (pin "5") (pinfunction "5_5") (pintype "passive"))
    )
    (net (code "611") (name "/RS_CTS") (class "Default")
      (node (ref "CN5") (pin "41") (pinfunction "41_41") (pintype "passive"))
    )
    (net (code "613") (name "/RS_RTS") (class "Default")
      (node (ref "CN5") (pin "43") (pinfunction "43_43") (pintype "passive"))
    )
    (net (code "615") (name "/RS_RXD") (class "Default")
      (node (ref "CN5") (pin "42") (pinfunction "42_42") (pintype "passive"))
    )
    (net (code "616") (name "/RS_TXD") (class "Default")
      (node (ref "CN5") (pin "44") (pinfunction "44_44") (pintype "passive"))
    )
    (net (code "622") (name "/RX+") (class "Default")
      (node (ref "CN3") (pin "3") (pinfunction "3_3") (pintype "passive"))
    )
    (net (code "623") (name "/RX-") (class "Default")
      (node (ref "CN3") (pin "6") (pinfunction "6_6") (pintype "passive"))
    )
    (net (code "624") (name "/RxFA-1+") (class "Default")
      (node (ref "CN2") (pin "160") (pinfunction "RxFA-1+_160") (pintype "output"))
    )
    (net (code "625") (name "/RxFA-1-") (class "Default")
      (node (ref "CN2") (pin "159") (pinfunction "RxFA-1-_159") (pintype "output"))
    )
    (net (code "626") (name "/RxFA-2+") (class "Default")
      (node (ref "CN2") (pin "154") (pinfunction "RxFA-2+_154") (pintype "output"))
    )
    (net (code "627") (name "/RxFA-2-") (class "Default")
      (node (ref "CN2") (pin "153") (pinfunction "RxFA-2-_153") (pintype "output"))
    )
    (net (code "628") (name "/RxFA-3+") (class "Default")
      (node (ref "CN2") (pin "23") (pinfunction "RxFA-3+_23") (pintype "output"))
    )
    (net (code "629") (name "/RxFA-3-") (class "Default")
      (node (ref "CN2") (pin "24") (pinfunction "RxFA-3-_24") (pintype "output"))
    )
    (net (code "630") (name "/RxFA-4+") (class "Default")
      (node (ref "CN2") (pin "148") (pinfunction "RxFA-4+_148") (pintype "output"))
    )
    (net (code "631") (name "/RxFA-4-") (class "Default")
      (node (ref "CN2") (pin "147") (pinfunction "RxFA-4-_147") (pintype "output"))
    )
    (net (code "632") (name "/RxFA-5+") (class "Default")
      (node (ref "CN2") (pin "32") (pinfunction "RxFA-5+_32") (pintype "output"))
    )
    (net (code "633") (name "/RxFA-5-") (class "Default")
      (node (ref "CN2") (pin "33") (pinfunction "RxFA-5-_33") (pintype "output"))
    )
    (net (code "634") (name "/RxFA-6+") (class "Default")
      (node (ref "CN2") (pin "142") (pinfunction "RxFA-6+_142") (pintype "output"))
    )
    (net (code "635") (name "/RxFA-6-") (class "Default")
      (node (ref "CN2") (pin "141") (pinfunction "RxFA-6-_141") (pintype "output"))
    )
    (net (code "636") (name "/RxFA-7+") (class "Default")
      (node (ref "CN2") (pin "38") (pinfunction "RxFA-7+_38") (pintype "output"))
    )
    (net (code "637") (name "/RxFA-7-") (class "Default")
      (node (ref "CN2") (pin "39") (pinfunction "RxFA-7-_39") (pintype "output"))
    )
    (net (code "638") (name "/RxFA-8+") (class "Default")
      (node (ref "CN2") (pin "136") (pinfunction "RxFA-8+_136") (pintype "output"))
    )
    (net (code "639") (name "/RxFA-8-") (class "Default")
      (node (ref "CN2") (pin "135") (pinfunction "RxFA-8-_135") (pintype "output"))
    )
    (net (code "642") (name "/RxFUA+") (class "Default")
      (node (ref "CN2") (pin "14") (pinfunction "RxFUA+_14") (pintype "output"))
      (node (ref "IC20") (pin "4") (pinfunction "/A_4") (pintype "input"))
      (node (ref "R76") (pin "2") (pinfunction "2_2") (pintype "passive"))
    )
    (net (code "643") (name "/RxFUA-") (class "Default")
      (node (ref "CN2") (pin "15") (pinfunction "RxFUA-_15") (pintype "output"))
      (node (ref "IC20") (pin "3") (pinfunction "A_3") (pintype "input"))
      (node (ref "R76") (pin "1") (pinfunction "1_1") (pintype "passive"))
    )
    (net (code "644") (name "/SHIELD") (class "Default")
      (node (ref "CN3") (pin "0") (pinfunction "case_0") (pintype "passive"))
    )
    (net (code "645") (name "/SMI_RX0") (class "Default")
      (node (ref "CN6") (pin "6") (pinfunction "6_6") (pintype "passive"))
    )
    (net (code "646") (name "/SMI_RX1") (class "Default")
      (node (ref "CN6") (pin "10") (pinfunction "10_10") (pintype "passive"))
    )
    (net (code "647") (name "/SMI_RX2") (class "Default")
      (node (ref "CN6") (pin "16") (pinfunction "16_16") (pintype "passive"))
    )
    (net (code "648") (name "/SMI_RX3") (class "Default")
      (node (ref "CN6") (pin "20") (pinfunction "20_20") (pintype "passive"))
    )
    (net (code "649") (name "/SMI_RX4") (class "Default")
      (node (ref "CN6") (pin "5") (pinfunction "5_5") (pintype "passive"))
    )
    (net (code "650") (name "/SMI_RX5") (class "Default")
      (node (ref "CN6") (pin "9") (pinfunction "9_9") (pintype "passive"))
    )
    (net (code "652") (name "/SMI_RX6") (class "Default")
      (node (ref "CN6") (pin "15") (pinfunction "15_15") (pintype "passive"))
    )
    (net (code "653") (name "/SMI_RX7") (class "Default")
      (node (ref "CN6") (pin "19") (pinfunction "19_19") (pintype "passive"))
    )
    (net (code "654") (name "/SMI_TX0") (class "Default")
      (node (ref "RP28") (pin "4") (pinfunction "A_4") (pintype "passive"))
    )
    (net (code "655") (name "/SMI_TX1") (class "Default")
      (node (ref "RP28") (pin "3") (pinfunction "A_3") (pintype "passive"))
    )
    (net (code "656") (name "/SMI_TX2") (class "Default")
      (node (ref "RP28") (pin "2") (pinfunction "A_2") (pintype "passive"))
    )
    (net (code "657") (name "/SMI_TX3") (class "Default")
      (node (ref "RP28") (pin "1") (pinfunction "A_1") (pintype "passive"))
    )
    (net (code "658") (name "/SMI_TX4") (class "Default")
      (node (ref "RP29") (pin "8") (pinfunction "B_8") (pintype "passive"))
    )
    (net (code "659") (name "/SMI_TX5") (class "Default")
      (node (ref "RP29") (pin "7") (pinfunction "B_7") (pintype "passive"))
    )
    (net (code "665") (name "/SMI_TX6") (class "Default")
      (node (ref "RP29") (pin "6") (pinfunction "B_6") (pintype "passive"))
    )
    (net (code "666") (name "/SMI_TX7") (class "Default")
      (node (ref "RP29") (pin "5") (pinfunction "B_5") (pintype "passive"))
    )
    (net (code "668") (name "/SPI0_SPCK") (class "Default")
      (node (ref "R74") (pin "1") (pinfunction "1_1") (pintype "passive"))
    )
    (net (code "669") (name "/SPI_SCK") (class "Default")
      (node (ref "R74") (pin "2") (pinfunction "2_2") (pintype "passive"))
    )
    (net (code "670") (name "/TD0") (class "Default")
      (node (ref "R70") (pin "2") (pinfunction "2_2") (pintype "passive"))
    )
    (net (code "671") (name "/TD1") (class "Default")
      (node (ref "R72") (pin "2") (pinfunction "2_2") (pintype "passive"))
    )
    (net (code "672") (name "/TK0") (class "Default")
      (node (ref "R69") (pin "2") (pinfunction "2_2") (pintype "passive"))
    )
    (net (code "673") (name "/TK1") (class "Default")
      (node (ref "R71") (pin "2") (pinfunction "2_2") (pintype "passive"))
    )
    (net (code "676") (name "/TX+") (class "Default")
      (node (ref "CN3") (pin "1") (pinfunction "1_1") (pintype "passive"))
    )
    (net (code "677") (name "/TX-") (class "Default")
      (node (ref "CN3") (pin "2") (pinfunction "2_2") (pintype "passive"))
    )
    (net (code "678") (name "/TxFA-1+") (class "Default")
      (node (ref "CN2") (pin "163") (pinfunction "TxFA-1+_163") (pintype "input"))
    )
    (net (code "679") (name "/TxFA-1-") (class "Default")
      (node (ref "CN2") (pin "162") (pinfunction "TxFA-1-_162") (pintype "input"))
    )
    (net (code "680") (name "/TxFA-2+") (class "Default")
      (node (ref "CN2") (pin "157") (pinfunction "TxFA-2+_157") (pintype "input"))
    )
    (net (code "681") (name "/TxFA-2-") (class "Default")
      (node (ref "CN2") (pin "156") (pinfunction "TxFA-2-_156") (pintype "input"))
    )
    (net (code "682") (name "/TxFA-3+") (class "Default")
      (node (ref "CN2") (pin "20") (pinfunction "TxFA-3+_20") (pintype "input"))
    )
    (net (code "683") (name "/TxFA-3-") (class "Default")
      (node (ref "CN2") (pin "21") (pinfunction "TxFA-3-_21") (pintype "input"))
    )
    (net (code "684") (name "/TxFA-4+") (class "Default")
      (node (ref "CN2") (pin "151") (pinfunction "TxFA-4+_151") (pintype "input"))
    )
    (net (code "685") (name "/TxFA-4-") (class "Default")
      (node (ref "CN2") (pin "150") (pinfunction "TxFA-4-_150") (pintype "input"))
    )
    (net (code "686") (name "/TxFA-5+") (class "Default")
      (node (ref "CN2") (pin "29") (pinfunction "TxFA-5+_29") (pintype "input"))
    )
    (net (code "687") (name "/TxFA-5-") (class "Default")
      (node (ref "CN2") (pin "30") (pinfunction "TxFA-5-_30") (pintype "input"))
    )
    (net (code "688") (name "/TxFA-6+") (class "Default")
      (node (ref "CN2") (pin "145") (pinfunction "TxFA-6+_145") (pintype "input"))
    )
    (net (code "689") (name "/TxFA-6-") (class "Default")
      (node (ref "CN2") (pin "144") (pinfunction "TxFA-6-_144") (pintype "input"))
    )
    (net (code "690") (name "/TxFA-7+") (class "Default")
      (node (ref "CN2") (pin "35") (pinfunction "TxFA-7+_35") (pintype "input"))
    )
    (net (code "691") (name "/TxFA-7-") (class "Default")
      (node (ref "CN2") (pin "36") (pinfunction "TxFA-7-_36") (pintype "input"))
    )
    (net (code "692") (name "/TxFA-8+") (class "Default")
      (node (ref "CN2") (pin "139") (pinfunction "TxFA-8+_139") (pintype "input"))
    )
    (net (code "693") (name "/TxFA-8-") (class "Default")
      (node (ref "CN2") (pin "138") (pinfunction "TxFA-8-_138") (pintype "input"))
    )
    (net (code "694") (name "/TxFUA+") (class "Default")
      (node (ref "CN2") (pin "11") (pinfunction "TxFUA+_11") (pintype "input"))
      (node (ref "IC19") (pin "4") (pinfunction "Q_4") (pintype "output"))
    )
    (net (code "695") (name "/TxFUA-") (class "Default")
      (node (ref "CN2") (pin "12") (pinfunction "TxFUA-_12") (pintype "input"))
      (node (ref "IC19") (pin "3") (pinfunction "/Q_3") (pintype "output"))
    )
    (net (code "696") (name "/UP0_RD0") (class "Default")
      (node (ref "CN4") (pin "26") (pinfunction "26_26") (pintype "passive"))
    )
    (net (code "697") (name "/UP0_RD1") (class "Default")
      (node (ref "CN4") (pin "28") (pinfunction "28_28") (pintype "passive"))
    )
    (net (code "698") (name "/UP0_RD2") (class "Default")
      (node (ref "CN4") (pin "30") (pinfunction "30_30") (pintype "passive"))
    )
    (net (code "699") (name "/UP0_RD3") (class "Default")
      (node (ref "CN4") (pin "32") (pinfunction "32_32") (pintype "passive"))
    )
    (net (code "700") (name "/UP0_RD4") (class "Default")
      (node (ref "CN4") (pin "34") (pinfunction "34_34") (pintype "passive"))
    )
    (net (code "701") (name "/UP0_RD5") (class "Default")
      (node (ref "CN4") (pin "38") (pinfunction "38_38") (pintype "passive"))
    )
    (net (code "702") (name "/UP0_RD6") (class "Default")
      (node (ref "CN4") (pin "40") (pinfunction "40_40") (pintype "passive"))
    )
    (net (code "703") (name "/UP0_RD7") (class "Default")
      (node (ref "CN4") (pin "42") (pinfunction "42_42") (pintype "passive"))
    )
    (net (code "705") (name "/UP0_RD8") (class "Default")
      (node (ref "CN4") (pin "44") (pinfunction "44_44") (pintype "passive"))
    )
    (net (code "706") (name "/UP0_RD9") (class "Default")
      (node (ref "CN4") (pin "46") (pinfunction "46_46") (pintype "passive"))
    )
    (net (code "707") (name "/UP0_TD0") (class "Default")
      (node (ref "CN11") (pin "15") (pinfunction "15_15") (pintype "passive"))
    )
    (net (code "708") (name "/UP0_TD1") (class "Default")
      (node (ref "CN11") (pin "17") (pinfunction "17_17") (pintype "passive"))
    )
    (net (code "709") (name "/UP0_TD2") (class "Default")
      (node (ref "CN11") (pin "19") (pinfunction "19_19") (pintype "passive"))
    )
    (net (code "710") (name "/UP0_TD3") (class "Default")
      (node (ref "CN11") (pin "21") (pinfunction "21_21") (pintype "passive"))
    )
    (net (code "711") (name "/UP0_TD4") (class "Default")
      (node (ref "CN11") (pin "23") (pinfunction "23_23") (pintype "passive"))
    )
    (net (code "712") (name "/UP0_TD5") (class "Default")
      (node (ref "CN11") (pin "27") (pinfunction "27_27") (pintype "passive"))
    )
    (net (code "713") (name "/UP0_TD6") (class "Default")
      (node (ref "CN11") (pin "29") (pinfunction "29_29") (pintype "passive"))
    )
    (net (code "714") (name "/UP0_TD7") (class "Default")
      (node (ref "CN11") (pin "31") (pinfunction "31_31") (pintype "passive"))
    )
    (net (code "716") (name "/UP0_TD8") (class "Default")
      (node (ref "CN11") (pin "33") (pinfunction "33_33") (pintype "passive"))
    )
    (net (code "717") (name "/UP0_TD9") (class "Default")
      (node (ref "CN11") (pin "35") (pinfunction "35_35") (pintype "passive"))
    )
    (net (code "718") (name "/UP1_RD0") (class "Default")
      (node (ref "CN4") (pin "2") (pinfunction "2_2") (pintype "passive"))
    )
    (net (code "719") (name "/UP1_RD1") (class "Default")
      (node (ref "CN4") (pin "4") (pinfunction "4_4") (pintype "passive"))
    )
    (net (code "720") (name "/UP1_RD2") (class "Default")
      (node (ref "CN4") (pin "6") (pinfunction "6_6") (pintype "passive"))
    )
    (net (code "721") (name "/UP1_RD3") (class "Default")
      (node (ref "CN4") (pin "8") (pinfunction "8_8") (pintype "passive"))
    )
    (net (code "722") (name "/UP1_RD4") (class "Default")
      (node (ref "CN4") (pin "10") (pinfunction "10_10") (pintype "passive"))
    )
    (net (code "723") (name "/UP1_RD5") (class "Default")
      (node (ref "CN4") (pin "14") (pinfunction "14_14") (pintype "passive"))
    )
    (net (code "724") (name "/UP1_RD6") (class "Default")
      (node (ref "CN4") (pin "16") (pinfunction "16_16") (pintype "passive"))
    )
    (net (code "725") (name "/UP1_RD7") (class "Default")
      (node (ref "CN4") (pin "18") (pinfunction "18_18") (pintype "passive"))
    )
    (net (code "738") (name "/UP1_RD8") (class "Default")
      (node (ref "CN4") (pin "20") (pinfunction "20_20") (pintype "passive"))
    )
    (net (code "743") (name "/UP1_RD9") (class "Default")
      (node (ref "CN4") (pin "22") (pinfunction "22_22") (pintype "passive"))
    )
    (net (code "744") (name "/UP1_TD0") (class "Default")
      (node (ref "CN11") (pin "18") (pinfunction "18_18") (pintype "passive"))
    )
    (net (code "745") (name "/UP1_TD1") (class "Default")
      (node (ref "CN11") (pin "20") (pinfunction "20_20") (pintype "passive"))
    )
    (net (code "746") (name "/UP1_TD2") (class "Default")
      (node (ref "CN11") (pin "22") (pinfunction "22_22") (pintype "passive"))
    )
    (net (code "747") (name "/UP1_TD3") (class "Default")
      (node (ref "CN11") (pin "24") (pinfunction "24_24") (pintype "passive"))
    )
    (net (code "748") (name "/UP1_TD4") (class "Default")
      (node (ref "CN11") (pin "26") (pinfunction "26_26") (pintype "passive"))
    )
    (net (code "749") (name "/UP1_TD5") (class "Default")
      (node (ref "CN11") (pin "30") (pinfunction "30_30") (pintype "passive"))
    )
    (net (code "750") (name "/UP1_TD6") (class "Default")
      (node (ref "CN11") (pin "32") (pinfunction "32_32") (pintype "passive"))
    )
    (net (code "751") (name "/UP1_TD7") (class "Default")
      (node (ref "CN11") (pin "34") (pinfunction "34_34") (pintype "passive"))
    )
    (net (code "752") (name "/UP1_TD8") (class "Default")
      (node (ref "CN11") (pin "36") (pinfunction "36_36") (pintype "passive"))
    )
    (net (code "753") (name "/UP1_TD9") (class "Default")
      (node (ref "CN11") (pin "38") (pinfunction "38_38") (pintype "passive"))
    )
    (net (code "754") (name "/UP_ENABLE0") (class "Default")
      (node (ref "CN11") (pin "43") (pinfunction "43_43") (pintype "passive"))
    )
    (net (code "755") (name "/UP_ENABLE1") (class "Default")
      (node (ref "CN11") (pin "42") (pinfunction "42_42") (pintype "passive"))
    )
    (net (code "758") (name "/UP_LOOPEN0") (class "Default")
      (node (ref "CN11") (pin "47") (pinfunction "47_47") (pintype "passive"))
    )
    (net (code "760") (name "/UP_LOOPEN1") (class "Default")
      (node (ref "CN11") (pin "48") (pinfunction "48_48") (pintype "passive"))
    )
    (net (code "761") (name "/UP_PRBSEN0") (class "Default")
      (node (ref "CN11") (pin "49") (pinfunction "49_49") (pintype "passive"))
    )
    (net (code "762") (name "/UP_PRBSEN1") (class "Default")
      (node (ref "CN11") (pin "41") (pinfunction "41_41") (pintype "passive"))
    )
    (net (code "763") (name "/UP_SFP_DETECT0") (class "Default")
      (node (ref "CN5") (pin "30") (pinfunction "30_30") (pintype "passive"))
    )
    (net (code "764") (name "/UP_SFP_DETECT1") (class "Default")
      (node (ref "CN5") (pin "16") (pinfunction "16_16") (pintype "passive"))
    )
    (net (code "766") (name "/UP_SFP_LOS0") (class "Default")
      (node (ref "CN5") (pin "28") (pinfunction "28_28") (pintype "passive"))
    )
    (net (code "767") (name "/UP_SFP_LOS1") (class "Default")
      (node (ref "CN5") (pin "14") (pinfunction "14_14") (pintype "passive"))
    )
    (net (code "771") (name "/UP_SFP_SCL0") (class "Default")
      (node (ref "CN5") (pin "38") (pinfunction "38_38") (pintype "passive"))
    )
    (net (code "772") (name "/UP_SFP_SCL1") (class "Default")
      (node (ref "CN5") (pin "24") (pinfunction "24_24") (pintype "passive"))
    )
    (net (code "773") (name "/UP_SFP_SDA0") (class "Default")
      (node (ref "CN5") (pin "36") (pinfunction "36_36") (pintype "passive"))
    )
    (net (code "774") (name "/UP_SFP_SDA1") (class "Default")
      (node (ref "CN5") (pin "22") (pinfunction "22_22") (pintype "passive"))
    )
    (net (code "777") (name "/UP_SFP_TX_DISABLE0") (class "Default")
      (node (ref "CN5") (pin "34") (pinfunction "34_34") (pintype "passive"))
    )
    (net (code "790") (name "/UP_SFP_TX_DISABLE1") (class "Default")
      (node (ref "CN5") (pin "20") (pinfunction "20_20") (pintype "passive"))
    )
    (net (code "791") (name "/UP_SFP_TX_FAULT0") (class "Default")
      (node (ref "CN5") (pin "32") (pinfunction "32_32") (pintype "passive"))
    )
    (net (code "792") (name "/UP_SFP_TX_FAULT1") (class "Default")
      (node (ref "CN5") (pin "18") (pinfunction "18_18") (pintype "passive"))
    )
    (net (code "793") (name "/UP_SYNCEN0") (class "Default")
      (node (ref "CN11") (pin "45") (pinfunction "45_45") (pintype "passive"))
    )
    (net (code "794") (name "/UP_SYNCEN1") (class "Default")
      (node (ref "CN11") (pin "46") (pinfunction "46_46") (pintype "passive"))
    )
    (net (code "795") (name "/UP_SYNC_PASS0") (class "Default")
      (node (ref "CN11") (pin "50") (pinfunction "50_50") (pintype "passive"))
    )
    (net (code "796") (name "/UP_SYNC_PASS1") (class "Default")
      (node (ref "CN11") (pin "44") (pinfunction "44_44") (pintype "passive"))
    )
    (net (code "797") (name "/UTCA_ENABLE#") (class "Default")
      (node (ref "CN2") (pin "41") (pinfunction "ENABLE#_41") (pintype "output"))
    )
    (net (code "798") (name "/UTCA_GA0") (class "Default")
      (node (ref "CN2") (pin "5") (pinfunction "GA0_5") (pintype "output"))
    )
    (net (code "799") (name "/UTCA_GA1") (class "Default")
      (node (ref "CN2") (pin "17") (pinfunction "GA1_17") (pintype "output"))
    )
    (net (code "800") (name "/UTCA_GA2") (class "Default")
      (node (ref "CN2") (pin "26") (pinfunction "GA2_26") (pintype "output"))
    )
    (net (code "801") (name "/UTCA_PWRON#") (class "Default")
      (node (ref "CN2") (pin "170") (pinfunction "PWR_ON_170") (pintype "input"))
      (node (ref "CN7") (pin "12") (pinfunction "12_12") (pintype "passive"))
    )
    (net (code "802") (name "/WD_DRXD") (class "Default")
      (node (ref "CN7") (pin "15") (pinfunction "15_15") (pintype "passive"))
    )
    (net (code "803") (name "/WD_DTXD") (class "Default")
      (node (ref "CN7") (pin "13") (pinfunction "13_13") (pintype "passive"))
    )
    (net (code "804") (name "/WD_IN_CLKB") (class "Default")
      (node (ref "CN4") (pin "5") (pinfunction "5_5") (pintype "passive"))
    )
    (net (code "805") (name "/WD_JTAG_TCK") (class "Default")
      (node (ref "CN7") (pin "17") (pinfunction "17_17") (pintype "passive"))
    )
    (net (code "806") (name "/WD_JTAG_TDI") (class "Default")
      (node (ref "CN7") (pin "21") (pinfunction "21_21") (pintype "passive"))
    )
    (net (code "807") (name "/WD_JTAG_TDO") (class "Default")
      (node (ref "CN7") (pin "25") (pinfunction "25_25") (pintype "passive"))
    )
    (net (code "808") (name "/WD_JTAG_TMS") (class "Default")
      (node (ref "CN7") (pin "19") (pinfunction "19_19") (pintype "passive"))
    )
    (net (code "809") (name "/WD_NRST") (class "Default")
      (node (ref "CN7") (pin "23") (pinfunction "23_23") (pintype "passive"))
    )
    (net (code "810") (name "/WD_OUT") (class "Default")
      (node (ref "CN4") (pin "3") (pinfunction "3_3") (pintype "passive"))
    )
    (net (code "811") (name "GND") (class "Default")
      (node (ref "C194") (pin "1") (pinfunction "1_1") (pintype "passive"))
      (node (ref "C195") (pin "1") (pinfunction "1_1") (pintype "passive"))
      (node (ref "CN11") (pin "1") (pinfunction "1_1") (pintype "passive"))
      (node (ref "CN11") (pin "12") (pinfunction "12_12") (pintype "passive"))
      (node (ref "CN11") (pin "13") (pinfunction "13_13") (pintype "passive"))
      (node (ref "CN11") (pin "16") (pinfunction "16_16") (pintype "passive"))
      (node (ref "CN11") (pin "2") (pinfunction "2_2") (pintype "passive"))
      (node (ref "CN11") (pin "25") (pinfunction "25_25") (pintype "passive"))
      (node (ref "CN11") (pin "28") (pinfunction "28_28") (pintype "passive"))
      (node (ref "CN11") (pin "37") (pinfunction "37_37") (pintype "passive"))
      (node (ref "CN11") (pin "39") (pinfunction "39_39") (pintype "passive"))
      (node (ref "CN11") (pin "40") (pinfunction "40_40") (pintype "passive"))
      (node (ref "CN11") (pin "7") (pinfunction "7_7") (pintype "passive"))
      (node (ref "CN11") (pin "8") (pinfunction "8_8") (pintype "passive"))
      (node (ref "CN2") (pin "1") (pinfunction "GND_1") (pintype "power_in"))
      (node (ref "CN2") (pin "10") (pinfunction "GND_10") (pintype "power_in"))
      (node (ref "CN2") (pin "101") (pinfunction "GND_101") (pintype "power_in"))
      (node (ref "CN2") (pin "104") (pinfunction "GND_104") (pintype "power_in"))
      (node (ref "CN2") (pin "107") (pinfunction "GND_107") (pintype "power_in"))
      (node (ref "CN2") (pin "110") (pinfunction "GND_110") (pintype "power_in"))
      (node (ref "CN2") (pin "113") (pinfunction "GND_113") (pintype "power_in"))
      (node (ref "CN2") (pin "116") (pinfunction "GND_116") (pintype "power_in"))
      (node (ref "CN2") (pin "119") (pinfunction "GND_119") (pintype "power_in"))
      (node (ref "CN2") (pin "122") (pinfunction "GND_122") (pintype "power_in"))
      (node (ref "CN2") (pin "125") (pinfunction "GND_125") (pintype "power_in"))
      (node (ref "CN2") (pin "128") (pinfunction "GND_128") (pintype "power_in"))
      (node (ref "CN2") (pin "13") (pinfunction "GND_13") (pintype "power_in"))
      (node (ref "CN2") (pin "131") (pinfunction "GND_131") (pintype "power_in"))
      (node (ref "CN2") (pin "134") (pinfunction "GND_134") (pintype "power_in"))
      (node (ref "CN2") (pin "137") (pinfunction "GND_137") (pintype "power_in"))
      (node (ref "CN2") (pin "140") (pinfunction "GND_140") (pintype "power_in"))
      (node (ref "CN2") (pin "143") (pinfunction "GND_143") (pintype "power_in"))
      (node (ref "CN2") (pin "146") (pinfunction "GND_146") (pintype "power_in"))
      (node (ref "CN2") (pin "149") (pinfunction "GND_149") (pintype "power_in"))
      (node (ref "CN2") (pin "152") (pinfunction "GND_152") (pintype "power_in"))
      (node (ref "CN2") (pin "155") (pinfunction "GND_155") (pintype "power_in"))
      (node (ref "CN2") (pin "158") (pinfunction "GND_158") (pintype "power_in"))
      (node (ref "CN2") (pin "16") (pinfunction "GND_16") (pintype "power_in"))
      (node (ref "CN2") (pin "161") (pinfunction "GND_161") (pintype "power_in"))
      (node (ref "CN2") (pin "164") (pinfunction "GND_164") (pintype "power_in"))
      (node (ref "CN2") (pin "19") (pinfunction "GND_19") (pintype "power_in"))
      (node (ref "CN2") (pin "22") (pinfunction "GND_22") (pintype "power_in"))
      (node (ref "CN2") (pin "25") (pinfunction "GND_25") (pintype "power_in"))
      (node (ref "CN2") (pin "28") (pinfunction "GND_28") (pintype "power_in"))
      (node (ref "CN2") (pin "31") (pinfunction "GND_31") (pintype "power_in"))
      (node (ref "CN2") (pin "34") (pinfunction "GND_34") (pintype "power_in"))
      (node (ref "CN2") (pin "37") (pinfunction "GND_37") (pintype "power_in"))
      (node (ref "CN2") (pin "40") (pinfunction "GND_40") (pintype "power_in"))
      (node (ref "CN2") (pin "43") (pinfunction "GND_43") (pintype "power_in"))
      (node (ref "CN2") (pin "46") (pinfunction "GND_46") (pintype "power_in"))
      (node (ref "CN2") (pin "49") (pinfunction "GND_49") (pintype "power_in"))
      (node (ref "CN2") (pin "52") (pinfunction "GND_52") (pintype "power_in"))
      (node (ref "CN2") (pin "55") (pinfunction "GND_55") (pintype "power_in"))
      (node (ref "CN2") (pin "58") (pinfunction "GND_58") (pintype "power_in"))
      (node (ref "CN2") (pin "61") (pinfunction "GND_61") (pintype "power_in"))
      (node (ref "CN2") (pin "64") (pinfunction "GND_64") (pintype "power_in"))
      (node (ref "CN2") (pin "67") (pinfunction "GND_67") (pintype "power_in"))
      (node (ref "CN2") (pin "7") (pinfunction "GND_7") (pintype "power_in"))
      (node (ref "CN2") (pin "70") (pinfunction "GND_70") (pintype "power_in"))
      (node (ref "CN2") (pin "73") (pinfunction "GND_73") (pintype "power_in"))
      (node (ref "CN2") (pin "76") (pinfunction "GND_76") (pintype "power_in"))
      (node (ref "CN2") (pin "79") (pinfunction "GND_79") (pintype "power_in"))
      (node (ref "CN2") (pin "82") (pinfunction "GND_82") (pintype "power_in"))
      (node (ref "CN2") (pin "85") (pinfunction "GND_85") (pintype "power_in"))
      (node (ref "CN2") (pin "86") (pinfunction "GND_86") (pintype "power_in"))
      (node (ref "CN2") (pin "89") (pinfunction "GND_89") (pintype "power_in"))
      (node (ref "CN2") (pin "92") (pinfunction "GND_92") (pintype "power_in"))
      (node (ref "CN2") (pin "95") (pinfunction "GND_95") (pintype "power_in"))
      (node (ref "CN2") (pin "98") (pinfunction "GND_98") (pintype "power_in"))
      (node (ref "CN4") (pin "1") (pinfunction "1_1") (pintype "passive"))
      (node (ref "CN4") (pin "12") (pinfunction "12_12") (pintype "passive"))
      (node (ref "CN4") (pin "15") (pinfunction "15_15") (pintype "passive"))
      (node (ref "CN4") (pin "24") (pinfunction "24_24") (pintype "passive"))
      (node (ref "CN4") (pin "25") (pinfunction "25_25") (pintype "passive"))
      (node (ref "CN4") (pin "35") (pinfunction "35_35") (pintype "passive"))
      (node (ref "CN4") (pin "36") (pinfunction "36_36") (pintype "passive"))
      (node (ref "CN4") (pin "37") (pinfunction "37_37") (pintype "passive"))
      (node (ref "CN4") (pin "39") (pinfunction "39_39") (pintype "passive"))
      (node (ref "CN4") (pin "43") (pinfunction "43_43") (pintype "passive"))
      (node (ref "CN4") (pin "45") (pinfunction "45_45") (pintype "passive"))
      (node (ref "CN4") (pin "47") (pinfunction "47_47") (pintype "passive"))
      (node (ref "CN4") (pin "48") (pinfunction "48_48") (pintype "passive"))
      (node (ref "CN4") (pin "49") (pinfunction "49_49") (pintype "passive"))
      (node (ref "CN4") (pin "50") (pinfunction "50_50") (pintype "passive"))
      (node (ref "CN5") (pin "21") (pinfunction "21_21") (pintype "passive"))
      (node (ref "CN5") (pin "26") (pinfunction "26_26") (pintype "passive"))
      (node (ref "CN5") (pin "33") (pinfunction "33_33") (pintype "passive"))
      (node (ref "CN5") (pin "49") (pinfunction "49_49") (pintype "passive"))
      (node (ref "CN5") (pin "50") (pinfunction "50_50") (pintype "passive"))
      (node (ref "CN6") (pin "13") (pinfunction "13_13") (pintype "passive"))
      (node (ref "CN6") (pin "14") (pinfunction "14_14") (pintype "passive"))
      (node (ref "CN6") (pin "23") (pinfunction "23_23") (pintype "passive"))
      (node (ref "CN6") (pin "24") (pinfunction "24_24") (pintype "passive"))
      (node (ref "CN6") (pin "29") (pinfunction "29_29") (pintype "passive"))
      (node (ref "CN6") (pin "30") (pinfunction "30_30") (pintype "passive"))
      (node (ref "CN7") (pin "1") (pinfunction "1_1") (pintype "passive"))
      (node (ref "CN7") (pin "2") (pinfunction "2_2") (pintype "passive"))
      (node (ref "D1") (pin "2") (pinfunction "K_2") (pintype "passive"))
      (node (ref "D2") (pin "2") (pinfunction "K_2") (pintype "passive"))
      (node (ref "D3") (pin "2") (pinfunction "K_2") (pintype "passive"))
      (node (ref "D4") (pin "2") (pinfunction "K_2") (pintype "passive"))
      (node (ref "IC19") (pin "2") (pinfunction "GND_2") (pintype "passive"))
      (node (ref "IC20") (pin "2") (pinfunction "GND_2") (pintype "passive"))
      (node (ref "R109") (pin "2") (pinfunction "2_2") (pintype "passive"))
      (node (ref "R110") (pin "1") (pinfunction "1_1") (pintype "passive"))
      (node (ref "R112") (pin "2") (pinfunction "2_2") (pintype "passive"))
      (node (ref "R114") (pin "2") (pinfunction "2_2") (pintype "passive"))
      (node (ref "R116") (pin "2") (pinfunction "2_2") (pintype "passive"))
      (node (ref "R78") (pin "2") (pinfunction "2_2") (pintype "passive"))
      (node (ref "R79") (pin "2") (pinfunction "2_2") (pintype "passive"))
      (node (ref "R81") (pin "2") (pinfunction "2_2") (pintype "passive"))
      (node (ref "S1") (pin "A") (pinfunction "A_A") (pintype "passive"))
      (node (ref "S1") (pin "C") (pinfunction "C_C") (pintype "passive"))
    )
    (net (code "812") (name "Net-(CN2C-PS0#)") (class "Default")
      (node (ref "CN2") (pin "83") (pinfunction "PS0#_83") (pintype "passive"))
      (node (ref "D13") (pin "2") (pinfunction "K_2") (pintype "passive"))
    )
    (net (code "813") (name "Net-(CN2C-PS1#)") (class "Default")
      (node (ref "CN2") (pin "3") (pinfunction "PS1#_3") (pintype "output"))
      (node (ref "D13") (pin "1") (pinfunction "A_1") (pintype "passive"))
    )
    (net (code "814") (name "Net-(D1-A)") (class "Default")
      (node (ref "D1") (pin "1") (pinfunction "A_1") (pintype "passive"))
      (node (ref "RP30") (pin "1") (pinfunction "A_1") (pintype "passive"))
    )
    (net (code "815") (name "Net-(D2-A)") (class "Default")
      (node (ref "D2") (pin "1") (pinfunction "A_1") (pintype "passive"))
      (node (ref "RP30") (pin "2") (pinfunction "A_2") (pintype "passive"))
    )
    (net (code "816") (name "Net-(D3-A)") (class "Default")
      (node (ref "D3") (pin "1") (pinfunction "A_1") (pintype "passive"))
      (node (ref "RP30") (pin "3") (pinfunction "A_3") (pintype "passive"))
    )
    (net (code "817") (name "Net-(D4-A)") (class "Default")
      (node (ref "D4") (pin "1") (pinfunction "A_1") (pintype "passive"))
      (node (ref "RP30") (pin "4") (pinfunction "A_4") (pintype "passive"))
    )
    (net (code "818") (name "Net-(R111-Pad2)") (class "Default")
      (node (ref "R111") (pin "2") (pinfunction "2_2") (pintype "passive"))
      (node (ref "R112") (pin "1") (pinfunction "1_1") (pintype "passive"))
    )
    (net (code "819") (name "Net-(R113-Pad2)") (class "Default")
      (node (ref "R113") (pin "2") (pinfunction "2_2") (pintype "passive"))
      (node (ref "R114") (pin "1") (pinfunction "1_1") (pintype "passive"))
    )
    (net (code "820") (name "Net-(R115-Pad2)") (class "Default")
      (node (ref "R115") (pin "2") (pinfunction "2_2") (pintype "passive"))
      (node (ref "R116") (pin "1") (pinfunction "1_1") (pintype "passive"))
    )
    (net (code "821") (name "Net-(RP6A-A)") (class "Default")
      (node (ref "D5") (pin "KG") (pinfunction "KG_KG") (pintype "passive"))
      (node (ref "RP6") (pin "1") (pinfunction "A_1") (pintype "passive"))
    )
    (net (code "822") (name "Net-(RP6B-A)") (class "Default")
      (node (ref "D5") (pin "KR") (pinfunction "KR_KR") (pintype "passive"))
      (node (ref "RP6") (pin "2") (pinfunction "A_2") (pintype "passive"))
    )
    (net (code "823") (name "Net-(RP6C-A)") (class "Default")
      (node (ref "D6") (pin "KG") (pinfunction "KG_KG") (pintype "passive"))
      (node (ref "RP6") (pin "3") (pinfunction "A_3") (pintype "passive"))
    )
    (net (code "824") (name "Net-(RP6D-A)") (class "Default")
      (node (ref "D6") (pin "KR") (pinfunction "KR_KR") (pintype "passive"))
      (node (ref "RP6") (pin "4") (pinfunction "A_4") (pintype "passive"))
    )
    (net (code "825") (name "Net-(RP7A-A)") (class "Default")
      (node (ref "D7") (pin "KG") (pinfunction "KG_KG") (pintype "passive"))
      (node (ref "RP7") (pin "1") (pinfunction "A_1") (pintype "passive"))
    )
    (net (code "826") (name "Net-(RP7B-A)") (class "Default")
      (node (ref "D7") (pin "KR") (pinfunction "KR_KR") (pintype "passive"))
      (node (ref "RP7") (pin "2") (pinfunction "A_2") (pintype "passive"))
    )
    (net (code "827") (name "Net-(RP7C-A)") (class "Default")
      (node (ref "D8") (pin "KG") (pinfunction "KG_KG") (pintype "passive"))
      (node (ref "RP7") (pin "3") (pinfunction "A_3") (pintype "passive"))
    )
    (net (code "828") (name "Net-(RP7D-A)") (class "Default")
      (node (ref "D8") (pin "KR") (pinfunction "KR_KR") (pintype "passive"))
      (node (ref "RP7") (pin "4") (pinfunction "A_4") (pintype "passive"))
    )
    (net (code "829") (name "Net-(RP8A-A)") (class "Default")
      (node (ref "D9") (pin "KG") (pinfunction "KG_KG") (pintype "passive"))
      (node (ref "RP8") (pin "1") (pinfunction "A_1") (pintype "passive"))
    )
    (net (code "830") (name "Net-(RP8B-A)") (class "Default")
      (node (ref "D9") (pin "KR") (pinfunction "KR_KR") (pintype "passive"))
      (node (ref "RP8") (pin "2") (pinfunction "A_2") (pintype "passive"))
    )
    (net (code "831") (name "Net-(RP8C-A)") (class "Default")
      (node (ref "D10") (pin "KG") (pinfunction "KG_KG") (pintype "passive"))
      (node (ref "RP8") (pin "3") (pinfunction "A_3") (pintype "passive"))
    )
    (net (code "832") (name "Net-(RP8D-A)") (class "Default")
      (node (ref "D10") (pin "KR") (pinfunction "KR_KR") (pintype "passive"))
      (node (ref "RP8") (pin "4") (pinfunction "A_4") (pintype "passive"))
    )
    (net (code "833") (name "Net-(RP9A-A)") (class "Default")
      (node (ref "D11") (pin "KG") (pinfunction "KG_KG") (pintype "passive"))
      (node (ref "RP9") (pin "1") (pinfunction "A_1") (pintype "passive"))
    )
    (net (code "834") (name "Net-(RP9B-A)") (class "Default")
      (node (ref "D11") (pin "KR") (pinfunction "KR_KR") (pintype "passive"))
      (node (ref "RP9") (pin "2") (pinfunction "A_2") (pintype "passive"))
    )
    (net (code "835") (name "Net-(RP9C-A)") (class "Default")
      (node (ref "D12") (pin "KG") (pinfunction "KG_KG") (pintype "passive"))
      (node (ref "RP9") (pin "3") (pinfunction "A_3") (pintype "passive"))
    )
    (net (code "836") (name "Net-(RP9D-A)") (class "Default")
      (node (ref "D12") (pin "KR") (pinfunction "KR_KR") (pintype "passive"))
      (node (ref "RP9") (pin "4") (pinfunction "A_4") (pintype "passive"))
    )
    (net (code "837") (name "Net-(RP28A-B)") (class "Default")
      (node (ref "CN6") (pin "22") (pinfunction "22_22") (pintype "passive"))
      (node (ref "RP28") (pin "8") (pinfunction "B_8") (pintype "passive"))
    )
    (net (code "838") (name "Net-(RP28B-B)") (class "Default")
      (node (ref "CN6") (pin "18") (pinfunction "18_18") (pintype "passive"))
      (node (ref "RP28") (pin "7") (pinfunction "B_7") (pintype "passive"))
    )
    (net (code "839") (name "Net-(RP28C-B)") (class "Default")
      (node (ref "CN6") (pin "12") (pinfunction "12_12") (pintype "passive"))
      (node (ref "RP28") (pin "6") (pinfunction "B_6") (pintype "passive"))
    )
    (net (code "840") (name "Net-(RP28D-B)") (class "Default")
      (node (ref "CN6") (pin "8") (pinfunction "8_8") (pintype "passive"))
      (node (ref "RP28") (pin "5") (pinfunction "B_5") (pintype "passive"))
    )
    (net (code "841") (name "Net-(RP29A-A)") (class "Default")
      (node (ref "CN6") (pin "7") (pinfunction "7_7") (pintype "passive"))
      (node (ref "RP29") (pin "1") (pinfunction "A_1") (pintype "passive"))
    )
    (net (code "842") (name "Net-(RP29B-A)") (class "Default")
      (node (ref "CN6") (pin "11") (pinfunction "11_11") (pintype "passive"))
      (node (ref "RP29") (pin "2") (pinfunction "A_2") (pintype "passive"))
    )
    (net (code "843") (name "Net-(RP29C-A)") (class "Default")
      (node (ref "CN6") (pin "17") (pinfunction "17_17") (pintype "passive"))
      (node (ref "RP29") (pin "3") (pinfunction "A_3") (pintype "passive"))
    )
    (net (code "844") (name "Net-(RP29D-A)") (class "Default")
      (node (ref "CN6") (pin "21") (pinfunction "21_21") (pintype "passive"))
      (node (ref "RP29") (pin "4") (pinfunction "A_4") (pintype "passive"))
    )
    (net (code "845") (name "unconnected-(CN2A-RxFA-9+-Pad47)") (class "Default")
      (node (ref "CN2") (pin "47") (pinfunction "RxFA-9+_47") (pintype "output"))
    )
    (net (code "846") (name "unconnected-(CN2A-RxFA-9--Pad48)") (class "Default")
      (node (ref "CN2") (pin "48") (pinfunction "RxFA-9-_48") (pintype "output"))
    )
    (net (code "847") (name "unconnected-(CN2A-RxFA-10+-Pad53)") (class "Default")
      (node (ref "CN2") (pin "53") (pinfunction "RxFA-10+_53") (pintype "output"))
    )
    (net (code "848") (name "unconnected-(CN2A-RxFA-10--Pad54)") (class "Default")
      (node (ref "CN2") (pin "54") (pinfunction "RxFA-10-_54") (pintype "output"))
    )
    (net (code "849") (name "unconnected-(CN2A-RxFA-11+-Pad62)") (class "Default")
      (node (ref "CN2") (pin "62") (pinfunction "RxFA-11+_62") (pintype "output"))
    )
    (net (code "850") (name "unconnected-(CN2A-RxFA-11--Pad63)") (class "Default")
      (node (ref "CN2") (pin "63") (pinfunction "RxFA-11-_63") (pintype "output"))
    )
    (net (code "851") (name "unconnected-(CN2A-RxFA-12+-Pad68)") (class "Default")
      (node (ref "CN2") (pin "68") (pinfunction "RxFA-12+_68") (pintype "output"))
    )
    (net (code "852") (name "unconnected-(CN2A-RxFA-12--Pad69)") (class "Default")
      (node (ref "CN2") (pin "69") (pinfunction "RxFA-12-_69") (pintype "output"))
    )
    (net (code "853") (name "unconnected-(CN2A-TxFA-9+-Pad44)") (class "Default")
      (node (ref "CN2") (pin "44") (pinfunction "TxFA-9+_44") (pintype "input+no_connect"))
    )
    (net (code "854") (name "unconnected-(CN2A-TxFA-9--Pad45)") (class "Default")
      (node (ref "CN2") (pin "45") (pinfunction "TxFA-9-_45") (pintype "input+no_connect"))
    )
    (net (code "855") (name "unconnected-(CN2A-TxFA-10+-Pad50)") (class "Default")
      (node (ref "CN2") (pin "50") (pinfunction "TxFA-10+_50") (pintype "input+no_connect"))
    )
    (net (code "856") (name "unconnected-(CN2A-TxFA-10--Pad51)") (class "Default")
      (node (ref "CN2") (pin "51") (pinfunction "TxFA-10-_51") (pintype "input+no_connect"))
    )
    (net (code "857") (name "unconnected-(CN2A-TxFA-11+-Pad59)") (class "Default")
      (node (ref "CN2") (pin "59") (pinfunction "TxFA-11+_59") (pintype "input+no_connect"))
    )
    (net (code "858") (name "unconnected-(CN2A-TxFA-11--Pad60)") (class "Default")
      (node (ref "CN2") (pin "60") (pinfunction "TxFA-11-_60") (pintype "input+no_connect"))
    )
    (net (code "859") (name "unconnected-(CN2A-TxFA-12+-Pad65)") (class "Default")
      (node (ref "CN2") (pin "65") (pinfunction "TxFA-12+_65") (pintype "input+no_connect"))
    )
    (net (code "860") (name "unconnected-(CN2A-TxFA-12--Pad66)") (class "Default")
      (node (ref "CN2") (pin "66") (pinfunction "TxFA-12-_66") (pintype "input+no_connect"))
    )
    (net (code "861") (name "unconnected-(CN2A-XOVER0+-Pad74)") (class "Default")
      (node (ref "CN2") (pin "74") (pinfunction "XOVER0+_74") (pintype "input+no_connect"))
    )
    (net (code "862") (name "unconnected-(CN2A-XOVER0--Pad75)") (class "Default")
      (node (ref "CN2") (pin "75") (pinfunction "XOVER0-_75") (pintype "input+no_connect"))
    )
    (net (code "863") (name "unconnected-(CN2A-XOVER1+-Pad77)") (class "Default")
      (node (ref "CN2") (pin "77") (pinfunction "XOVER1+_77") (pintype "bidirectional"))
    )
    (net (code "864") (name "unconnected-(CN2A-XOVER1--Pad78)") (class "Default")
      (node (ref "CN2") (pin "78") (pinfunction "XOVER1-_78") (pintype "bidirectional"))
    )
    (net (code "865") (name "unconnected-(CN2A-XOVER2+-Pad80)") (class "Default")
      (node (ref "CN2") (pin "80") (pinfunction "XOVER2+_80") (pintype "output"))
    )
    (net (code "866") (name "unconnected-(CN2A-XOVER2--Pad81)") (class "Default")
      (node (ref "CN2") (pin "81") (pinfunction "XOVER2-_81") (pintype "output"))
    )
    (net (code "867") (name "unconnected-(CN2C-IPMBL-SCL-9-Pad97)") (class "Default")
      (node (ref "CN2") (pin "97") (pinfunction "IPMBL-SCL-9_97") (pintype "open_collector"))
    )
    (net (code "868") (name "unconnected-(CN2C-IPMBL-SCL-10-Pad94)") (class "Default")
      (node (ref "CN2") (pin "94") (pinfunction "IPMBL-SCL-10_94") (pintype "open_collector"))
    )
    (net (code "869") (name "unconnected-(CN2C-IPMBL-SCL-11-Pad91)") (class "Default")
      (node (ref "CN2") (pin "91") (pinfunction "IPMBL-SCL-11_91") (pintype "open_collector"))
    )
    (net (code "870") (name "unconnected-(CN2C-IPMBL-SCL-12-Pad88)") (class "Default")
      (node (ref "CN2") (pin "88") (pinfunction "IPMBL-SCL-12_88") (pintype "open_collector"))
    )
    (net (code "871") (name "unconnected-(CN2C-IPMBL-SDA-9-Pad96)") (class "Default")
      (node (ref "CN2") (pin "96") (pinfunction "IPMBL-SDA-9_96") (pintype "open_collector"))
    )
    (net (code "872") (name "unconnected-(CN2C-IPMBL-SDA-10-Pad93)") (class "Default")
      (node (ref "CN2") (pin "93") (pinfunction "IPMBL-SDA-10_93") (pintype "open_collector"))
    )
    (net (code "873") (name "unconnected-(CN2C-IPMBL-SDA-11-Pad90)") (class "Default")
      (node (ref "CN2") (pin "90") (pinfunction "IPMBL-SDA-11_90") (pintype "open_collector"))
    )
    (net (code "874") (name "unconnected-(CN2C-IPMBL-SDA-12-Pad87)") (class "Default")
      (node (ref "CN2") (pin "87") (pinfunction "IPMBL-SDA-12_87") (pintype "open_collector"))
    )
    (net (code "875") (name "unconnected-(CN2C-RSVD-Pad6)") (class "Default")
      (node (ref "CN2") (pin "6") (pinfunction "RSVD_6") (pintype "tri_state"))
    )
    (net (code "876") (name "unconnected-(CN2C-RSVD-Pad8)") (class "Default")
      (node (ref "CN2") (pin "8") (pinfunction "RSVD_8") (pintype "tri_state"))
    )
    (net (code "877") (name "unconnected-(CN2C-RSVD-Pad132)") (class "Default")
      (node (ref "CN2") (pin "132") (pinfunction "RSVD_132") (pintype "tri_state"))
    )
    (net (code "878") (name "unconnected-(CN2C-TCK-Pad165)") (class "Default")
      (node (ref "CN2") (pin "165") (pinfunction "TCK_165") (pintype "bidirectional+no_connect"))
    )
    (net (code "879") (name "unconnected-(CN2C-TDI-Pad169)") (class "Default")
      (node (ref "CN2") (pin "169") (pinfunction "TDI_169") (pintype "bidirectional+no_connect"))
    )
    (net (code "880") (name "unconnected-(CN2C-TDO-Pad168)") (class "Default")
      (node (ref "CN2") (pin "168") (pinfunction "TDO_168") (pintype "bidirectional+no_connect"))
    )
    (net (code "881") (name "unconnected-(CN2C-TMREQ#-Pad133)") (class "Default")
      (node (ref "CN2") (pin "133") (pinfunction "TMREQ#_133") (pintype "input+no_connect"))
    )
    (net (code "882") (name "unconnected-(CN2C-TMS-Pad166)") (class "Default")
      (node (ref "CN2") (pin "166") (pinfunction "TMS_166") (pintype "bidirectional+no_connect"))
    )
    (net (code "883") (name "unconnected-(CN2C-TRST#-Pad167)") (class "Default")
      (node (ref "CN2") (pin "167") (pinfunction "TRST#_167") (pintype "bidirectional+no_connect"))
    )
    (net (code "884") (name "unconnected-(CN3-Pad4)") (class "Default")
      (node (ref "CN3") (pin "4") (pinfunction "4_4") (pintype "passive"))
    )
    (net (code "885") (name "unconnected-(CN3-Pad5)") (class "Default")
      (node (ref "CN3") (pin "5") (pinfunction "5_5") (pintype "passive"))
    )
    (net (code "886") (name "unconnected-(CN3-Pad7)") (class "Default")
      (node (ref "CN3") (pin "7") (pinfunction "7_7") (pintype "passive"))
    )
    (net (code "887") (name "unconnected-(CN3-Pad8)") (class "Default")
      (node (ref "CN3") (pin "8") (pinfunction "8_8") (pintype "passive"))
    )
    (net (code "888") (name "unconnected-(CN6-Pad25)") (class "Default")
      (node (ref "CN6") (pin "25") (pinfunction "25_25") (pintype "passive"))
    )
    (net (code "889") (name "unconnected-(CN6-Pad26)") (class "Default")
      (node (ref "CN6") (pin "26") (pinfunction "26_26") (pintype "passive"))
    )
    (net (code "890") (name "unconnected-(CN6-Pad27)") (class "Default")
      (node (ref "CN6") (pin "27") (pinfunction "27_27") (pintype "passive"))
    )
    (net (code "891") (name "unconnected-(CN6-Pad28)") (class "Default")
      (node (ref "CN6") (pin "28") (pinfunction "28_28") (pintype "passive"))
    )
  )
)
